# qc_board_V3.net
KiCad netlist of a schematic drawn in EAGLE
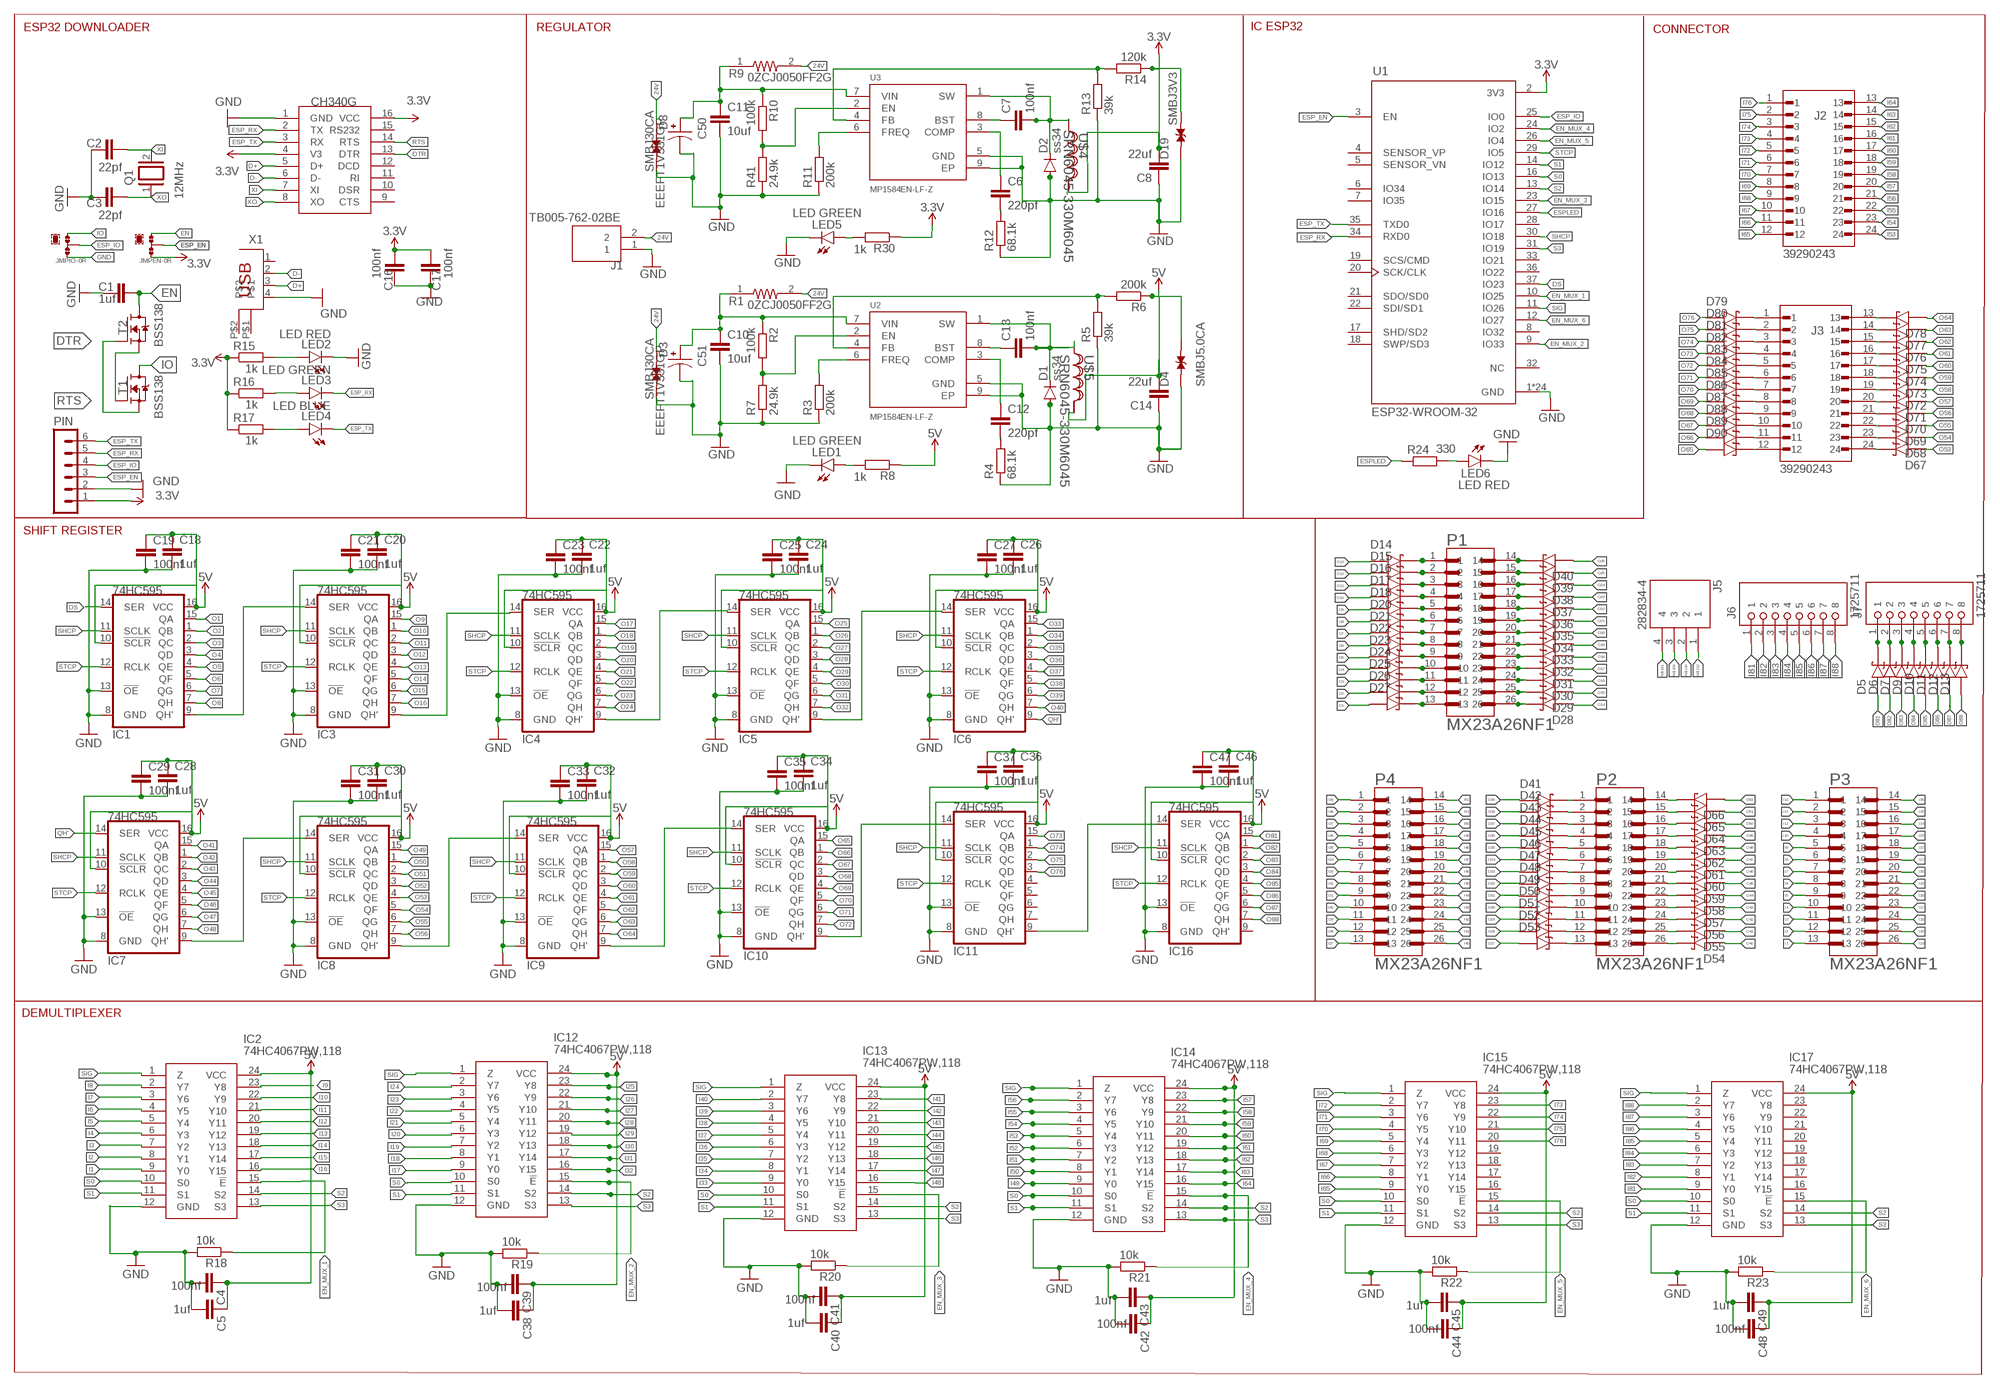
[diagram p0: schematic, sheet 1]

(export (version "E")
  (design (tool "Eeschema 10.0.6"))
  (components
    (comp (ref "C1")
      (value "1uf")
      (footprint "eagle-import:C0805")
      (libsource (lib "eagle-import") (part "C-EUC0805"))
    )
    (comp (ref "C2")
      (value "22pf")
      (footprint "eagle-import:C0805")
      (libsource (lib "eagle-import") (part "C-EUC0805"))
    )
    (comp (ref "C3")
      (value "22pf")
      (footprint "eagle-import:C0805")
      (libsource (lib "eagle-import") (part "C-EUC0805"))
    )
    (comp (ref "C4")
      (value "100nf")
      (footprint "eagle-import:C0805")
      (libsource (lib "eagle-import") (part "C-EUC0805"))
    )
    (comp (ref "C5")
      (value "1uf")
      (footprint "eagle-import:C0805")
      (libsource (lib "eagle-import") (part "C-EUC0805"))
    )
    (comp (ref "C6")
      (value "220pf")
      (footprint "eagle-import:C0805")
      (libsource (lib "eagle-import") (part "C-EUC0805"))
    )
    (comp (ref "C7")
      (value "100nf")
      (footprint "eagle-import:C0805")
      (libsource (lib "eagle-import") (part "C-EUC0805"))
    )
    (comp (ref "C8")
      (value "22uf")
      (footprint "eagle-import:C0805")
      (libsource (lib "eagle-import") (part "C-EUC0805"))
    )
    (comp (ref "C10")
      (value "10uf")
      (footprint "eagle-import:C0805")
      (libsource (lib "eagle-import") (part "C-EUC0805"))
    )
    (comp (ref "C11")
      (value "10uf")
      (footprint "eagle-import:C0805")
      (libsource (lib "eagle-import") (part "C-EUC0805"))
    )
    (comp (ref "C12")
      (value "220pf")
      (footprint "eagle-import:C0805")
      (libsource (lib "eagle-import") (part "C-EUC0805"))
    )
    (comp (ref "C13")
      (value "100nf")
      (footprint "eagle-import:C0805")
      (libsource (lib "eagle-import") (part "C-EUC0805"))
    )
    (comp (ref "C14")
      (value "22uf")
      (footprint "eagle-import:C0805")
      (libsource (lib "eagle-import") (part "C-EUC0805"))
    )
    (comp (ref "C16")
      (value "100nf")
      (footprint "eagle-import:C0805")
      (libsource (lib "eagle-import") (part "C-EUC0805"))
    )
    (comp (ref "C17")
      (value "100nf")
      (footprint "eagle-import:C0805")
      (libsource (lib "eagle-import") (part "C-EUC0805"))
    )
    (comp (ref "C18")
      (value "1uf")
      (footprint "eagle-import:C0805")
      (libsource (lib "eagle-import") (part "C-EUC0805"))
    )
    (comp (ref "C19")
      (value "100nf")
      (footprint "eagle-import:C0805")
      (libsource (lib "eagle-import") (part "C-EUC0805"))
    )
    (comp (ref "C20")
      (value "1uf")
      (footprint "eagle-import:C0805")
      (libsource (lib "eagle-import") (part "C-EUC0805"))
    )
    (comp (ref "C21")
      (value "100nf")
      (footprint "eagle-import:C0805")
      (libsource (lib "eagle-import") (part "C-EUC0805"))
    )
    (comp (ref "C22")
      (value "1uf")
      (footprint "eagle-import:C0805")
      (libsource (lib "eagle-import") (part "C-EUC0805"))
    )
    (comp (ref "C23")
      (value "100nf")
      (footprint "eagle-import:C0805")
      (libsource (lib "eagle-import") (part "C-EUC0805"))
    )
    (comp (ref "C24")
      (value "1uf")
      (footprint "eagle-import:C0805")
      (libsource (lib "eagle-import") (part "C-EUC0805"))
    )
    (comp (ref "C25")
      (value "100nf")
      (footprint "eagle-import:C0805")
      (libsource (lib "eagle-import") (part "C-EUC0805"))
    )
    (comp (ref "C26")
      (value "1uf")
      (footprint "eagle-import:C0805")
      (libsource (lib "eagle-import") (part "C-EUC0805"))
    )
    (comp (ref "C27")
      (value "100nf")
      (footprint "eagle-import:C0805")
      (libsource (lib "eagle-import") (part "C-EUC0805"))
    )
    (comp (ref "C28")
      (value "1uf")
      (footprint "eagle-import:C0805")
      (libsource (lib "eagle-import") (part "C-EUC0805"))
    )
    (comp (ref "C29")
      (value "100nf")
      (footprint "eagle-import:C0805")
      (libsource (lib "eagle-import") (part "C-EUC0805"))
    )
    (comp (ref "C30")
      (value "1uf")
      (footprint "eagle-import:C0805")
      (libsource (lib "eagle-import") (part "C-EUC0805"))
    )
    (comp (ref "C31")
      (value "100nf")
      (footprint "eagle-import:C0805")
      (libsource (lib "eagle-import") (part "C-EUC0805"))
    )
    (comp (ref "C32")
      (value "1uf")
      (footprint "eagle-import:C0805")
      (libsource (lib "eagle-import") (part "C-EUC0805"))
    )
    (comp (ref "C33")
      (value "100nf")
      (footprint "eagle-import:C0805")
      (libsource (lib "eagle-import") (part "C-EUC0805"))
    )
    (comp (ref "C34")
      (value "1uf")
      (footprint "eagle-import:C0805")
      (libsource (lib "eagle-import") (part "C-EUC0805"))
    )
    (comp (ref "C35")
      (value "100nf")
      (footprint "eagle-import:C0805")
      (libsource (lib "eagle-import") (part "C-EUC0805"))
    )
    (comp (ref "C36")
      (value "1uf")
      (footprint "eagle-import:C0805")
      (libsource (lib "eagle-import") (part "C-EUC0805"))
    )
    (comp (ref "C37")
      (value "100nf")
      (footprint "eagle-import:C0805")
      (libsource (lib "eagle-import") (part "C-EUC0805"))
    )
    (comp (ref "C38")
      (value "1uf")
      (footprint "eagle-import:C0805")
      (libsource (lib "eagle-import") (part "C-EUC0805"))
    )
    (comp (ref "C39")
      (value "100nf")
      (footprint "eagle-import:C0805")
      (libsource (lib "eagle-import") (part "C-EUC0805"))
    )
    (comp (ref "C40")
      (value "1uf")
      (footprint "eagle-import:C0805")
      (libsource (lib "eagle-import") (part "C-EUC0805"))
    )
    (comp (ref "C41")
      (value "100nf")
      (footprint "eagle-import:C0805")
      (libsource (lib "eagle-import") (part "C-EUC0805"))
    )
    (comp (ref "C42")
      (value "100nf")
      (footprint "eagle-import:C0805")
      (libsource (lib "eagle-import") (part "C-EUC0805"))
    )
    (comp (ref "C43")
      (value "1uf")
      (footprint "eagle-import:C0805")
      (libsource (lib "eagle-import") (part "C-EUC0805"))
    )
    (comp (ref "C44")
      (value "100nf")
      (footprint "eagle-import:C0805")
      (libsource (lib "eagle-import") (part "C-EUC0805"))
    )
    (comp (ref "C45")
      (value "1uf")
      (footprint "eagle-import:C0805")
      (libsource (lib "eagle-import") (part "C-EUC0805"))
    )
    (comp (ref "C46")
      (value "1uf")
      (footprint "eagle-import:C0805")
      (libsource (lib "eagle-import") (part "C-EUC0805"))
    )
    (comp (ref "C47")
      (value "100nf")
      (footprint "eagle-import:C0805")
      (libsource (lib "eagle-import") (part "C-EUC0805"))
    )
    (comp (ref "C48")
      (value "100nf")
      (footprint "eagle-import:C0805")
      (libsource (lib "eagle-import") (part "C-EUC0805"))
    )
    (comp (ref "C49")
      (value "1uf")
      (footprint "eagle-import:C0805")
      (libsource (lib "eagle-import") (part "C-EUC0805"))
    )
    (comp (ref "C50")
      (value "EEEFT1V331GP")
      (footprint "eagle-import:CAP_EEEFT1V331GP")
      (fields (field (name "MF") "Panasonic"))
      (libsource (lib "eagle-import") (part "EEEFT1V331GP"))
    )
    (comp (ref "C51")
      (value "EEEFT1V331GP")
      (footprint "eagle-import:CAP_EEEFT1V331GP")
      (fields (field (name "MF") "Panasonic"))
      (libsource (lib "eagle-import") (part "EEEFT1V331GP"))
    )
    (comp (ref "D1")
      (value "ss34")
      (footprint "eagle-import:SMB")
      (libsource (lib "eagle-import") (part "DIODE-SMB"))
    )
    (comp (ref "D2")
      (value "ss34")
      (footprint "eagle-import:SMB")
      (libsource (lib "eagle-import") (part "DIODE-SMB"))
    )
    (comp (ref "D3")
      (value "SMBJ30CA")
      (footprint "eagle-import:DIOM4336X265N")
      (fields (field (name "MF") "Taiwan Semiconductor Corporation"))
      (libsource (lib "eagle-import") (part "SMBJ30CA"))
    )
    (comp (ref "D4")
      (value "SMBJ5.0CA")
      (footprint "eagle-import:DIOM4336X265N")
      (fields (field (name "MF") "Taiwan Semiconductor"))
      (libsource (lib "eagle-import") (part "SMBJ5.0CA"))
    )
    (comp (ref "D5")
      (value "1N5819HW-7")
      (footprint "eagle-import:SOD3715X145N")
      (fields (field (name "MF") "Diodes Inc."))
      (libsource (lib "eagle-import") (part "1N5819HW-7"))
    )
    (comp (ref "D6")
      (value "1N5819HW-7")
      (footprint "eagle-import:SOD3715X145N")
      (fields (field (name "MF") "Diodes Inc."))
      (libsource (lib "eagle-import") (part "1N5819HW-7"))
    )
    (comp (ref "D7")
      (value "1N5819HW-7")
      (footprint "eagle-import:SOD3715X145N")
      (fields (field (name "MF") "Diodes Inc."))
      (libsource (lib "eagle-import") (part "1N5819HW-7"))
    )
    (comp (ref "D8")
      (value "SMBJ30CA")
      (footprint "eagle-import:DIOM4336X265N")
      (fields (field (name "MF") "Taiwan Semiconductor Corporation"))
      (libsource (lib "eagle-import") (part "SMBJ30CA"))
    )
    (comp (ref "D9")
      (value "1N5819HW-7")
      (footprint "eagle-import:SOD3715X145N")
      (fields (field (name "MF") "Diodes Inc."))
      (libsource (lib "eagle-import") (part "1N5819HW-7"))
    )
    (comp (ref "D10")
      (value "1N5819HW-7")
      (footprint "eagle-import:SOD3715X145N")
      (fields (field (name "MF") "Diodes Inc."))
      (libsource (lib "eagle-import") (part "1N5819HW-7"))
    )
    (comp (ref "D11")
      (value "1N5819HW-7")
      (footprint "eagle-import:SOD3715X145N")
      (fields (field (name "MF") "Diodes Inc."))
      (libsource (lib "eagle-import") (part "1N5819HW-7"))
    )
    (comp (ref "D12")
      (value "1N5819HW-7")
      (footprint "eagle-import:SOD3715X145N")
      (fields (field (name "MF") "Diodes Inc."))
      (libsource (lib "eagle-import") (part "1N5819HW-7"))
    )
    (comp (ref "D13")
      (value "1N5819HW-7")
      (footprint "eagle-import:SOD3715X145N")
      (fields (field (name "MF") "Diodes Inc."))
      (libsource (lib "eagle-import") (part "1N5819HW-7"))
    )
    (comp (ref "D14")
      (value "1N5819HW-7")
      (footprint "eagle-import:SOD3715X145N")
      (fields (field (name "MF") "Diodes Inc."))
      (libsource (lib "eagle-import") (part "1N5819HW-7"))
    )
    (comp (ref "D15")
      (value "1N5819HW-7")
      (footprint "eagle-import:SOD3715X145N")
      (fields (field (name "MF") "Diodes Inc."))
      (libsource (lib "eagle-import") (part "1N5819HW-7"))
    )
    (comp (ref "D16")
      (value "1N5819HW-7")
      (footprint "eagle-import:SOD3715X145N")
      (fields (field (name "MF") "Diodes Inc."))
      (libsource (lib "eagle-import") (part "1N5819HW-7"))
    )
    (comp (ref "D17")
      (value "1N5819HW-7")
      (footprint "eagle-import:SOD3715X145N")
      (fields (field (name "MF") "Diodes Inc."))
      (libsource (lib "eagle-import") (part "1N5819HW-7"))
    )
    (comp (ref "D18")
      (value "1N5819HW-7")
      (footprint "eagle-import:SOD3715X145N")
      (fields (field (name "MF") "Diodes Inc."))
      (libsource (lib "eagle-import") (part "1N5819HW-7"))
    )
    (comp (ref "D19")
      (value "SMBJ3V3")
      (footprint "eagle-import:DIOM4336X265N")
      (fields (field (name "MF") "Taiwan Semiconductor Corporation") (field (name "MP") "SMBJ30CA"))
      (libsource (lib "eagle-import") (part "SMBJ3V3"))
    )
    (comp (ref "D20")
      (value "1N5819HW-7")
      (footprint "eagle-import:SOD3715X145N")
      (fields (field (name "MF") "Diodes Inc."))
      (libsource (lib "eagle-import") (part "1N5819HW-7"))
    )
    (comp (ref "D21")
      (value "1N5819HW-7")
      (footprint "eagle-import:SOD3715X145N")
      (fields (field (name "MF") "Diodes Inc."))
      (libsource (lib "eagle-import") (part "1N5819HW-7"))
    )
    (comp (ref "D22")
      (value "1N5819HW-7")
      (footprint "eagle-import:SOD3715X145N")
      (fields (field (name "MF") "Diodes Inc."))
      (libsource (lib "eagle-import") (part "1N5819HW-7"))
    )
    (comp (ref "D23")
      (value "1N5819HW-7")
      (footprint "eagle-import:SOD3715X145N")
      (fields (field (name "MF") "Diodes Inc."))
      (libsource (lib "eagle-import") (part "1N5819HW-7"))
    )
    (comp (ref "D24")
      (value "1N5819HW-7")
      (footprint "eagle-import:SOD3715X145N")
      (fields (field (name "MF") "Diodes Inc."))
      (libsource (lib "eagle-import") (part "1N5819HW-7"))
    )
    (comp (ref "D25")
      (value "1N5819HW-7")
      (footprint "eagle-import:SOD3715X145N")
      (fields (field (name "MF") "Diodes Inc."))
      (libsource (lib "eagle-import") (part "1N5819HW-7"))
    )
    (comp (ref "D26")
      (value "1N5819HW-7")
      (footprint "eagle-import:SOD3715X145N")
      (fields (field (name "MF") "Diodes Inc."))
      (libsource (lib "eagle-import") (part "1N5819HW-7"))
    )
    (comp (ref "D27")
      (value "1N5819HW-7")
      (footprint "eagle-import:SOD3715X145N")
      (fields (field (name "MF") "Diodes Inc."))
      (libsource (lib "eagle-import") (part "1N5819HW-7"))
    )
    (comp (ref "D28")
      (value "1N5819HW-7")
      (footprint "eagle-import:SOD3715X145N")
      (fields (field (name "MF") "Diodes Inc."))
      (libsource (lib "eagle-import") (part "1N5819HW-7"))
    )
    (comp (ref "D29")
      (value "1N5819HW-7")
      (footprint "eagle-import:SOD3715X145N")
      (fields (field (name "MF") "Diodes Inc."))
      (libsource (lib "eagle-import") (part "1N5819HW-7"))
    )
    (comp (ref "D30")
      (value "1N5819HW-7")
      (footprint "eagle-import:SOD3715X145N")
      (fields (field (name "MF") "Diodes Inc."))
      (libsource (lib "eagle-import") (part "1N5819HW-7"))
    )
    (comp (ref "D31")
      (value "1N5819HW-7")
      (footprint "eagle-import:SOD3715X145N")
      (fields (field (name "MF") "Diodes Inc."))
      (libsource (lib "eagle-import") (part "1N5819HW-7"))
    )
    (comp (ref "D32")
      (value "1N5819HW-7")
      (footprint "eagle-import:SOD3715X145N")
      (fields (field (name "MF") "Diodes Inc."))
      (libsource (lib "eagle-import") (part "1N5819HW-7"))
    )
    (comp (ref "D33")
      (value "1N5819HW-7")
      (footprint "eagle-import:SOD3715X145N")
      (fields (field (name "MF") "Diodes Inc."))
      (libsource (lib "eagle-import") (part "1N5819HW-7"))
    )
    (comp (ref "D34")
      (value "1N5819HW-7")
      (footprint "eagle-import:SOD3715X145N")
      (fields (field (name "MF") "Diodes Inc."))
      (libsource (lib "eagle-import") (part "1N5819HW-7"))
    )
    (comp (ref "D35")
      (value "1N5819HW-7")
      (footprint "eagle-import:SOD3715X145N")
      (fields (field (name "MF") "Diodes Inc."))
      (libsource (lib "eagle-import") (part "1N5819HW-7"))
    )
    (comp (ref "D36")
      (value "1N5819HW-7")
      (footprint "eagle-import:SOD3715X145N")
      (fields (field (name "MF") "Diodes Inc."))
      (libsource (lib "eagle-import") (part "1N5819HW-7"))
    )
    (comp (ref "D37")
      (value "1N5819HW-7")
      (footprint "eagle-import:SOD3715X145N")
      (fields (field (name "MF") "Diodes Inc."))
      (libsource (lib "eagle-import") (part "1N5819HW-7"))
    )
    (comp (ref "D38")
      (value "1N5819HW-7")
      (footprint "eagle-import:SOD3715X145N")
      (fields (field (name "MF") "Diodes Inc."))
      (libsource (lib "eagle-import") (part "1N5819HW-7"))
    )
    (comp (ref "D39")
      (value "1N5819HW-7")
      (footprint "eagle-import:SOD3715X145N")
      (fields (field (name "MF") "Diodes Inc."))
      (libsource (lib "eagle-import") (part "1N5819HW-7"))
    )
    (comp (ref "D40")
      (value "1N5819HW-7")
      (footprint "eagle-import:SOD3715X145N")
      (fields (field (name "MF") "Diodes Inc."))
      (libsource (lib "eagle-import") (part "1N5819HW-7"))
    )
    (comp (ref "D41")
      (value "1N5819HW-7")
      (footprint "eagle-import:SOD3715X145N")
      (fields (field (name "MF") "Diodes Inc."))
      (libsource (lib "eagle-import") (part "1N5819HW-7"))
    )
    (comp (ref "D42")
      (value "1N5819HW-7")
      (footprint "eagle-import:SOD3715X145N")
      (fields (field (name "MF") "Diodes Inc."))
      (libsource (lib "eagle-import") (part "1N5819HW-7"))
    )
    (comp (ref "D43")
      (value "1N5819HW-7")
      (footprint "eagle-import:SOD3715X145N")
      (fields (field (name "MF") "Diodes Inc."))
      (libsource (lib "eagle-import") (part "1N5819HW-7"))
    )
    (comp (ref "D44")
      (value "1N5819HW-7")
      (footprint "eagle-import:SOD3715X145N")
      (fields (field (name "MF") "Diodes Inc."))
      (libsource (lib "eagle-import") (part "1N5819HW-7"))
    )
    (comp (ref "D45")
      (value "1N5819HW-7")
      (footprint "eagle-import:SOD3715X145N")
      (fields (field (name "MF") "Diodes Inc."))
      (libsource (lib "eagle-import") (part "1N5819HW-7"))
    )
    (comp (ref "D46")
      (value "1N5819HW-7")
      (footprint "eagle-import:SOD3715X145N")
      (fields (field (name "MF") "Diodes Inc."))
      (libsource (lib "eagle-import") (part "1N5819HW-7"))
    )
    (comp (ref "D47")
      (value "1N5819HW-7")
      (footprint "eagle-import:SOD3715X145N")
      (fields (field (name "MF") "Diodes Inc."))
      (libsource (lib "eagle-import") (part "1N5819HW-7"))
    )
    (comp (ref "D48")
      (value "1N5819HW-7")
      (footprint "eagle-import:SOD3715X145N")
      (fields (field (name "MF") "Diodes Inc."))
      (libsource (lib "eagle-import") (part "1N5819HW-7"))
    )
    (comp (ref "D49")
      (value "1N5819HW-7")
      (footprint "eagle-import:SOD3715X145N")
      (fields (field (name "MF") "Diodes Inc."))
      (libsource (lib "eagle-import") (part "1N5819HW-7"))
    )
    (comp (ref "D50")
      (value "1N5819HW-7")
      (footprint "eagle-import:SOD3715X145N")
      (fields (field (name "MF") "Diodes Inc."))
      (libsource (lib "eagle-import") (part "1N5819HW-7"))
    )
    (comp (ref "D51")
      (value "1N5819HW-7")
      (footprint "eagle-import:SOD3715X145N")
      (fields (field (name "MF") "Diodes Inc."))
      (libsource (lib "eagle-import") (part "1N5819HW-7"))
    )
    (comp (ref "D52")
      (value "1N5819HW-7")
      (footprint "eagle-import:SOD3715X145N")
      (fields (field (name "MF") "Diodes Inc."))
      (libsource (lib "eagle-import") (part "1N5819HW-7"))
    )
    (comp (ref "D53")
      (value "1N5819HW-7")
      (footprint "eagle-import:SOD3715X145N")
      (fields (field (name "MF") "Diodes Inc."))
      (libsource (lib "eagle-import") (part "1N5819HW-7"))
    )
    (comp (ref "D54")
      (value "1N5819HW-7")
      (footprint "eagle-import:SOD3715X145N")
      (fields (field (name "MF") "Diodes Inc."))
      (libsource (lib "eagle-import") (part "1N5819HW-7"))
    )
    (comp (ref "D55")
      (value "1N5819HW-7")
      (footprint "eagle-import:SOD3715X145N")
      (fields (field (name "MF") "Diodes Inc."))
      (libsource (lib "eagle-import") (part "1N5819HW-7"))
    )
    (comp (ref "D56")
      (value "1N5819HW-7")
      (footprint "eagle-import:SOD3715X145N")
      (fields (field (name "MF") "Diodes Inc."))
      (libsource (lib "eagle-import") (part "1N5819HW-7"))
    )
    (comp (ref "D57")
      (value "1N5819HW-7")
      (footprint "eagle-import:SOD3715X145N")
      (fields (field (name "MF") "Diodes Inc."))
      (libsource (lib "eagle-import") (part "1N5819HW-7"))
    )
    (comp (ref "D58")
      (value "1N5819HW-7")
      (footprint "eagle-import:SOD3715X145N")
      (fields (field (name "MF") "Diodes Inc."))
      (libsource (lib "eagle-import") (part "1N5819HW-7"))
    )
    (comp (ref "D59")
      (value "1N5819HW-7")
      (footprint "eagle-import:SOD3715X145N")
      (fields (field (name "MF") "Diodes Inc."))
      (libsource (lib "eagle-import") (part "1N5819HW-7"))
    )
    (comp (ref "D60")
      (value "1N5819HW-7")
      (footprint "eagle-import:SOD3715X145N")
      (fields (field (name "MF") "Diodes Inc."))
      (libsource (lib "eagle-import") (part "1N5819HW-7"))
    )
    (comp (ref "D61")
      (value "1N5819HW-7")
      (footprint "eagle-import:SOD3715X145N")
      (fields (field (name "MF") "Diodes Inc."))
      (libsource (lib "eagle-import") (part "1N5819HW-7"))
    )
    (comp (ref "D62")
      (value "1N5819HW-7")
      (footprint "eagle-import:SOD3715X145N")
      (fields (field (name "MF") "Diodes Inc."))
      (libsource (lib "eagle-import") (part "1N5819HW-7"))
    )
    (comp (ref "D63")
      (value "1N5819HW-7")
      (footprint "eagle-import:SOD3715X145N")
      (fields (field (name "MF") "Diodes Inc."))
      (libsource (lib "eagle-import") (part "1N5819HW-7"))
    )
    (comp (ref "D64")
      (value "1N5819HW-7")
      (footprint "eagle-import:SOD3715X145N")
      (fields (field (name "MF") "Diodes Inc."))
      (libsource (lib "eagle-import") (part "1N5819HW-7"))
    )
    (comp (ref "D65")
      (value "1N5819HW-7")
      (footprint "eagle-import:SOD3715X145N")
      (fields (field (name "MF") "Diodes Inc."))
      (libsource (lib "eagle-import") (part "1N5819HW-7"))
    )
    (comp (ref "D66")
      (value "1N5819HW-7")
      (footprint "eagle-import:SOD3715X145N")
      (fields (field (name "MF") "Diodes Inc."))
      (libsource (lib "eagle-import") (part "1N5819HW-7"))
    )
    (comp (ref "D67")
      (value "1N5819HW-7")
      (footprint "eagle-import:SOD3715X145N")
      (fields (field (name "MF") "Diodes Inc."))
      (libsource (lib "eagle-import") (part "1N5819HW-7"))
    )
    (comp (ref "D68")
      (value "1N5819HW-7")
      (footprint "eagle-import:SOD3715X145N")
      (fields (field (name "MF") "Diodes Inc."))
      (libsource (lib "eagle-import") (part "1N5819HW-7"))
    )
    (comp (ref "D69")
      (value "1N5819HW-7")
      (footprint "eagle-import:SOD3715X145N")
      (fields (field (name "MF") "Diodes Inc."))
      (libsource (lib "eagle-import") (part "1N5819HW-7"))
    )
    (comp (ref "D70")
      (value "1N5819HW-7")
      (footprint "eagle-import:SOD3715X145N")
      (fields (field (name "MF") "Diodes Inc."))
      (libsource (lib "eagle-import") (part "1N5819HW-7"))
    )
    (comp (ref "D71")
      (value "1N5819HW-7")
      (footprint "eagle-import:SOD3715X145N")
      (fields (field (name "MF") "Diodes Inc."))
      (libsource (lib "eagle-import") (part "1N5819HW-7"))
    )
    (comp (ref "D72")
      (value "1N5819HW-7")
      (footprint "eagle-import:SOD3715X145N")
      (fields (field (name "MF") "Diodes Inc."))
      (libsource (lib "eagle-import") (part "1N5819HW-7"))
    )
    (comp (ref "D73")
      (value "1N5819HW-7")
      (footprint "eagle-import:SOD3715X145N")
      (fields (field (name "MF") "Diodes Inc."))
      (libsource (lib "eagle-import") (part "1N5819HW-7"))
    )
    (comp (ref "D74")
      (value "1N5819HW-7")
      (footprint "eagle-import:SOD3715X145N")
      (fields (field (name "MF") "Diodes Inc."))
      (libsource (lib "eagle-import") (part "1N5819HW-7"))
    )
    (comp (ref "D75")
      (value "1N5819HW-7")
      (footprint "eagle-import:SOD3715X145N")
      (fields (field (name "MF") "Diodes Inc."))
      (libsource (lib "eagle-import") (part "1N5819HW-7"))
    )
    (comp (ref "D76")
      (value "1N5819HW-7")
      (footprint "eagle-import:SOD3715X145N")
      (fields (field (name "MF") "Diodes Inc."))
      (libsource (lib "eagle-import") (part "1N5819HW-7"))
    )
    (comp (ref "D77")
      (value "1N5819HW-7")
      (footprint "eagle-import:SOD3715X145N")
      (fields (field (name "MF") "Diodes Inc."))
      (libsource (lib "eagle-import") (part "1N5819HW-7"))
    )
    (comp (ref "D78")
      (value "1N5819HW-7")
      (footprint "eagle-import:SOD3715X145N")
      (fields (field (name "MF") "Diodes Inc."))
      (libsource (lib "eagle-import") (part "1N5819HW-7"))
    )
    (comp (ref "D79")
      (value "1N5819HW-7")
      (footprint "eagle-import:SOD3715X145N")
      (fields (field (name "MF") "Diodes Inc."))
      (libsource (lib "eagle-import") (part "1N5819HW-7"))
    )
    (comp (ref "D80")
      (value "1N5819HW-7")
      (footprint "eagle-import:SOD3715X145N")
      (fields (field (name "MF") "Diodes Inc."))
      (libsource (lib "eagle-import") (part "1N5819HW-7"))
    )
    (comp (ref "D81")
      (value "1N5819HW-7")
      (footprint "eagle-import:SOD3715X145N")
      (fields (field (name "MF") "Diodes Inc."))
      (libsource (lib "eagle-import") (part "1N5819HW-7"))
    )
    (comp (ref "D82")
      (value "1N5819HW-7")
      (footprint "eagle-import:SOD3715X145N")
      (fields (field (name "MF") "Diodes Inc."))
      (libsource (lib "eagle-import") (part "1N5819HW-7"))
    )
    (comp (ref "D83")
      (value "1N5819HW-7")
      (footprint "eagle-import:SOD3715X145N")
      (fields (field (name "MF") "Diodes Inc."))
      (libsource (lib "eagle-import") (part "1N5819HW-7"))
    )
    (comp (ref "D84")
      (value "1N5819HW-7")
      (footprint "eagle-import:SOD3715X145N")
      (fields (field (name "MF") "Diodes Inc."))
      (libsource (lib "eagle-import") (part "1N5819HW-7"))
    )
    (comp (ref "D85")
      (value "1N5819HW-7")
      (footprint "eagle-import:SOD3715X145N")
      (fields (field (name "MF") "Diodes Inc."))
      (libsource (lib "eagle-import") (part "1N5819HW-7"))
    )
    (comp (ref "D86")
      (value "1N5819HW-7")
      (footprint "eagle-import:SOD3715X145N")
      (fields (field (name "MF") "Diodes Inc."))
      (libsource (lib "eagle-import") (part "1N5819HW-7"))
    )
    (comp (ref "D87")
      (value "1N5819HW-7")
      (footprint "eagle-import:SOD3715X145N")
      (fields (field (name "MF") "Diodes Inc."))
      (libsource (lib "eagle-import") (part "1N5819HW-7"))
    )
    (comp (ref "D88")
      (value "1N5819HW-7")
      (footprint "eagle-import:SOD3715X145N")
      (fields (field (name "MF") "Diodes Inc."))
      (libsource (lib "eagle-import") (part "1N5819HW-7"))
    )
    (comp (ref "D89")
      (value "1N5819HW-7")
      (footprint "eagle-import:SOD3715X145N")
      (fields (field (name "MF") "Diodes Inc."))
      (libsource (lib "eagle-import") (part "1N5819HW-7"))
    )
    (comp (ref "D90")
      (value "1N5819HW-7")
      (footprint "eagle-import:SOD3715X145N")
      (fields (field (name "MF") "Diodes Inc."))
      (libsource (lib "eagle-import") (part "1N5819HW-7"))
    )
    (comp (ref "IC1")
      (value "74HC595")
      (footprint "eagle-import:SO16")
      (fields (field (name "MF") "Nexperia"))
      (libsource (lib "eagle-import") (part "74HC595"))
    )
    (comp (ref "IC2")
      (value "74HC4067PW,118")
      (footprint "eagle-import:SOP65P640X110-24N")
      (fields (field (name "MOUSER_PART_NUMBER") "771-74HC4067PW-T"))
      (libsource (lib "eagle-import") (part "74HC4067PW,118"))
    )
    (comp (ref "IC3")
      (value "74HC595")
      (footprint "eagle-import:SO16")
      (fields (field (name "MF") "Nexperia"))
      (libsource (lib "eagle-import") (part "74HC595"))
    )
    (comp (ref "IC4")
      (value "74HC595")
      (footprint "eagle-import:SO16")
      (fields (field (name "MF") "Nexperia"))
      (libsource (lib "eagle-import") (part "74HC595"))
    )
    (comp (ref "IC5")
      (value "74HC595")
      (footprint "eagle-import:SO16")
      (fields (field (name "MF") "Nexperia"))
      (libsource (lib "eagle-import") (part "74HC595"))
    )
    (comp (ref "IC6")
      (value "74HC595")
      (footprint "eagle-import:SO16")
      (fields (field (name "MF") "Nexperia"))
      (libsource (lib "eagle-import") (part "74HC595"))
    )
    (comp (ref "IC7")
      (value "74HC595")
      (footprint "eagle-import:SO16")
      (fields (field (name "MF") "Nexperia"))
      (libsource (lib "eagle-import") (part "74HC595"))
    )
    (comp (ref "IC8")
      (value "74HC595")
      (footprint "eagle-import:SO16")
      (fields (field (name "MF") "Nexperia"))
      (libsource (lib "eagle-import") (part "74HC595"))
    )
    (comp (ref "IC9")
      (value "74HC595")
      (footprint "eagle-import:SO16")
      (fields (field (name "MF") "Nexperia"))
      (libsource (lib "eagle-import") (part "74HC595"))
    )
    (comp (ref "IC10")
      (value "74HC595")
      (footprint "eagle-import:SO16")
      (fields (field (name "MF") "Nexperia"))
      (libsource (lib "eagle-import") (part "74HC595"))
    )
    (comp (ref "IC11")
      (value "74HC595")
      (footprint "eagle-import:SO16")
      (fields (field (name "MF") "Nexperia"))
      (libsource (lib "eagle-import") (part "74HC595"))
    )
    (comp (ref "IC12")
      (value "74HC4067PW,118")
      (footprint "eagle-import:SOP65P640X110-24N")
      (fields (field (name "MOUSER_PART_NUMBER") "771-74HC4067PW-T"))
      (libsource (lib "eagle-import") (part "74HC4067PW,118"))
    )
    (comp (ref "IC13")
      (value "74HC4067PW,118")
      (footprint "eagle-import:SOP65P640X110-24N")
      (fields (field (name "MOUSER_PART_NUMBER") "771-74HC4067PW-T"))
      (libsource (lib "eagle-import") (part "74HC4067PW,118"))
    )
    (comp (ref "IC14")
      (value "74HC4067PW,118")
      (footprint "eagle-import:SOP65P640X110-24N")
      (fields (field (name "MOUSER_PART_NUMBER") "771-74HC4067PW-T"))
      (libsource (lib "eagle-import") (part "74HC4067PW,118"))
    )
    (comp (ref "IC15")
      (value "74HC4067PW,118")
      (footprint "eagle-import:SOP65P640X110-24N")
      (fields (field (name "MOUSER_PART_NUMBER") "771-74HC4067PW-T"))
      (libsource (lib "eagle-import") (part "74HC4067PW,118"))
    )
    (comp (ref "IC16")
      (value "74HC595")
      (footprint "eagle-import:SO16")
      (fields (field (name "MF") "Nexperia"))
      (libsource (lib "eagle-import") (part "74HC595"))
    )
    (comp (ref "IC17")
      (value "74HC4067PW,118")
      (footprint "eagle-import:SOP65P640X110-24N")
      (fields (field (name "MOUSER_PART_NUMBER") "771-74HC4067PW-T"))
      (libsource (lib "eagle-import") (part "74HC4067PW,118"))
    )
    (comp (ref "J1")
      (value "TB005-762-02BE")
      (footprint "eagle-import:CUI_TB005-762-02BE")
      (fields (field (name "MF") "Same Sky"))
      (libsource (lib "eagle-import") (part "TB005-762-02BE"))
    )
    (comp (ref "J2")
      (value "39290243")
      (footprint "eagle-import:MOLEX_39290243")
      (fields (field (name "MF") "Molex Connector") (field (name "MP") "39-29-0243"))
      (libsource (lib "eagle-import") (part "39290243"))
    )
    (comp (ref "J3")
      (value "39290243")
      (footprint "eagle-import:MOLEX_39290243")
      (fields (field (name "MF") "Molex Connector") (field (name "MP") "39-29-0243"))
      (libsource (lib "eagle-import") (part "39290243"))
    )
    (comp (ref "J5")
      (value "282834-4")
      (footprint "eagle-import:TE_282834-4")
      (fields (field (name "MF") "TE Connectivity"))
      (libsource (lib "eagle-import") (part "282834-4"))
    )
    (comp (ref "J6")
      (value "1725711")
      (footprint "eagle-import:PHOENIX_1725711")
      (fields (field (name "MF") "Phoenix Contact"))
      (libsource (lib "eagle-import") (part "1725711"))
    )
    (comp (ref "J7")
      (value "1725711")
      (footprint "eagle-import:PHOENIX_1725711")
      (fields (field (name "MF") "Phoenix Contact"))
      (libsource (lib "eagle-import") (part "1725711"))
    )
    (comp (ref "JMPEN")
      (value "0R-JUMPB")
      (footprint "eagle-import:B0R-JMP")
      (libsource (lib "eagle-import") (part "0R-JUMPB"))
    )
    (comp (ref "JMPIO")
      (value "0R-JUMPB")
      (footprint "eagle-import:B0R-JMP")
      (libsource (lib "eagle-import") (part "0R-JUMPB"))
    )
    (comp (ref "LED1")
      (value "LED GREEN")
      (footprint "eagle-import:CHIP-LED0805")
      (libsource (lib "eagle-import") (part "LEDCHIP-LED0805"))
    )
    (comp (ref "LED2")
      (value "LED RED")
      (footprint "eagle-import:CHIPLED_0805")
      (libsource (lib "eagle-import") (part "LEDCHIPLED_0805"))
    )
    (comp (ref "LED3")
      (value "LED GREEN")
      (footprint "eagle-import:CHIPLED_0805")
      (libsource (lib "eagle-import") (part "LEDCHIPLED_0805"))
    )
    (comp (ref "LED4")
      (value "LED BLUE")
      (footprint "eagle-import:CHIPLED_0805")
      (libsource (lib "eagle-import") (part "LEDCHIPLED_0805"))
    )
    (comp (ref "LED5")
      (value "LED GREEN")
      (footprint "eagle-import:CHIP-LED0805")
      (libsource (lib "eagle-import") (part "LEDCHIP-LED0805"))
    )
    (comp (ref "LED6")
      (value "LED RED")
      (footprint "eagle-import:CHIP-LED0805")
      (libsource (lib "eagle-import") (part "LEDCHIP-LED0805"))
    )
    (comp (ref "P1")
      (value "MX23A26NF1")
      (footprint "eagle-import:JAE_MX23A26NF1")
      (fields (field (name "MF") "JAE Electronics"))
      (libsource (lib "eagle-import") (part "MX23A26NF1"))
    )
    (comp (ref "P2")
      (value "MX23A26NF1")
      (footprint "eagle-import:JAE_MX23A26NF1")
      (fields (field (name "MF") "JAE Electronics"))
      (libsource (lib "eagle-import") (part "MX23A26NF1"))
    )
    (comp (ref "P3")
      (value "MX23A26NF1")
      (footprint "eagle-import:JAE_MX23A26NF1")
      (fields (field (name "MF") "JAE Electronics"))
      (libsource (lib "eagle-import") (part "MX23A26NF1"))
    )
    (comp (ref "P4")
      (value "MX23A26NF1")
      (footprint "eagle-import:JAE_MX23A26NF1")
      (fields (field (name "MF") "JAE Electronics"))
      (libsource (lib "eagle-import") (part "MX23A26NF1"))
    )
    (comp (ref "PIN")
      (value "MA06-1")
      (footprint "eagle-import:MA06-1")
      (libsource (lib "eagle-import") (part "MA06-1"))
    )
    (comp (ref "Q1")
      (value "12MHz")
      (footprint "eagle-import:QS")
      (libsource (lib "eagle-import") (part "XTAL/S"))
    )
    (comp (ref "R1")
      (value "0ZCJ0050FF2G")
      (footprint "eagle-import:RESC3216X125N")
      (fields (field (name "MF") "Bel Fuse"))
      (libsource (lib "eagle-import") (part "0ZCJ0050FF2G"))
    )
    (comp (ref "R2")
      (value "100k")
      (footprint "eagle-import:R0805")
      (libsource (lib "eagle-import") (part "rcl_334_R-EU_R0805"))
    )
    (comp (ref "R3")
      (value "200k")
      (footprint "eagle-import:R0805")
      (libsource (lib "eagle-import") (part "rcl_334_R-EU_R0805"))
    )
    (comp (ref "R4")
      (value "68.1k")
      (footprint "eagle-import:R0805")
      (libsource (lib "eagle-import") (part "rcl_334_R-EU_R0805"))
    )
    (comp (ref "R5")
      (value "39k")
      (footprint "eagle-import:R0805")
      (libsource (lib "eagle-import") (part "rcl_334_R-EU_R0805"))
    )
    (comp (ref "R6")
      (value "200k")
      (footprint "eagle-import:R0805")
      (libsource (lib "eagle-import") (part "rcl_334_R-EU_R0805"))
    )
    (comp (ref "R7")
      (value "24.9k")
      (footprint "eagle-import:R0805")
      (libsource (lib "eagle-import") (part "rcl_334_R-EU_R0805"))
    )
    (comp (ref "R8")
      (value "1k")
      (footprint "eagle-import:R0805")
      (libsource (lib "eagle-import") (part "rcl_334_R-EU_R0805"))
    )
    (comp (ref "R9")
      (value "0ZCJ0050FF2G")
      (footprint "eagle-import:RESC3216X125N")
      (fields (field (name "MF") "Bel Fuse"))
      (libsource (lib "eagle-import") (part "0ZCJ0050FF2G"))
    )
    (comp (ref "R10")
      (value "100k")
      (footprint "eagle-import:R0805")
      (libsource (lib "eagle-import") (part "rcl_334_R-EU_R0805"))
    )
    (comp (ref "R11")
      (value "200k")
      (footprint "eagle-import:R0805")
      (libsource (lib "eagle-import") (part "rcl_334_R-EU_R0805"))
    )
    (comp (ref "R12")
      (value "68.1k")
      (footprint "eagle-import:R0805")
      (libsource (lib "eagle-import") (part "rcl_334_R-EU_R0805"))
    )
    (comp (ref "R13")
      (value "39k")
      (footprint "eagle-import:R0805")
      (libsource (lib "eagle-import") (part "rcl_334_R-EU_R0805"))
    )
    (comp (ref "R14")
      (value "120k")
      (footprint "eagle-import:R0805")
      (libsource (lib "eagle-import") (part "rcl_334_R-EU_R0805"))
    )
    (comp (ref "R15")
      (value "1k")
      (footprint "eagle-import:M0805")
      (libsource (lib "eagle-import") (part "R-EU_M0805"))
    )
    (comp (ref "R16")
      (value "1k")
      (footprint "eagle-import:M0805")
      (libsource (lib "eagle-import") (part "R-EU_M0805"))
    )
    (comp (ref "R17")
      (value "1k")
      (footprint "eagle-import:M0805")
      (libsource (lib "eagle-import") (part "R-EU_M0805"))
    )
    (comp (ref "R18")
      (value "10k")
      (footprint "eagle-import:M0805")
      (libsource (lib "eagle-import") (part "R-EU_M0805"))
    )
    (comp (ref "R19")
      (value "10k")
      (footprint "eagle-import:M0805")
      (libsource (lib "eagle-import") (part "R-EU_M0805"))
    )
    (comp (ref "R20")
      (value "10k")
      (footprint "eagle-import:M0805")
      (libsource (lib "eagle-import") (part "R-EU_M0805"))
    )
    (comp (ref "R21")
      (value "10k")
      (footprint "eagle-import:M0805")
      (libsource (lib "eagle-import") (part "R-EU_M0805"))
    )
    (comp (ref "R22")
      (value "10k")
      (footprint "eagle-import:M0805")
      (libsource (lib "eagle-import") (part "R-EU_M0805"))
    )
    (comp (ref "R23")
      (value "10k")
      (footprint "eagle-import:M0805")
      (libsource (lib "eagle-import") (part "R-EU_M0805"))
    )
    (comp (ref "R24")
      (value "330")
      (footprint "eagle-import:R0805")
      (libsource (lib "eagle-import") (part "rcl_334_R-EU_R0805"))
    )
    (comp (ref "R30")
      (value "1k")
      (footprint "eagle-import:R0805")
      (libsource (lib "eagle-import") (part "rcl_334_R-EU_R0805"))
    )
    (comp (ref "R41")
      (value "24.9k")
      (footprint "eagle-import:R0805")
      (libsource (lib "eagle-import") (part "rcl_334_R-EU_R0805"))
    )
    (comp (ref "T1")
      (value "BSS138")
      (footprint "eagle-import:SOT95P240X111-3N")
      (fields (field (name "MF") "ON Semiconductor"))
      (libsource (lib "eagle-import") (part "BSS138"))
    )
    (comp (ref "T2")
      (value "BSS138")
      (footprint "eagle-import:SOT95P240X111-3N")
      (fields (field (name "MF") "ON Semiconductor"))
      (libsource (lib "eagle-import") (part "BSS138"))
    )
    (comp (ref "U$3")
      (value "CH340G")
      (footprint "eagle-import:SOIC16")
      (libsource (lib "eagle-import") (part "CH340G"))
    )
    (comp (ref "U$4")
      (value "SRN6045-330M6045")
      (footprint "eagle-import:SRN6045")
      (fields (field (name "MF") "Bourns") (field (name "MP") "SRN6045-330M"))
      (libsource (lib "eagle-import") (part "SRN6045-330M6045"))
    )
    (comp (ref "U$5")
      (value "SRN6045-330M6045")
      (footprint "eagle-import:SRN6045")
      (fields (field (name "MF") "Bourns") (field (name "MP") "SRN6045-330M"))
      (libsource (lib "eagle-import") (part "SRN6045-330M6045"))
    )
    (comp (ref "U1")
      (value "ESP32-WROOM-32")
      (footprint "eagle-import:MODULE_ESP32-WROOM-32")
      (fields (field (name "MF") "Espressif Systems"))
      (libsource (lib "eagle-import") (part "ESP32-WROOM-32"))
    )
    (comp (ref "U2")
      (value "MP1584EN-LF-Z")
      (footprint "eagle-import:SOIC127P600X170-9N")
      (fields (field (name "MF") "Monolithic Power"))
      (libsource (lib "eagle-import") (part "MP1584EN-LF-Z"))
    )
    (comp (ref "U3")
      (value "MP1584EN-LF-Z")
      (footprint "eagle-import:SOIC127P600X170-9N")
      (fields (field (name "MF") "Monolithic Power"))
      (libsource (lib "eagle-import") (part "MP1584EN-LF-Z"))
    )
    (comp (ref "X1")
      (value "PN61729")
      (footprint "eagle-import:PN61729")
      (libsource (lib "eagle-import") (part "PN61729"))
    )
  )
  (nets
    (net (code "1") (name "3.3V") (class "Default")
      (node (ref "C16") (pin "1") (pinfunction "1_1") (pintype "passive"))
      (node (ref "C17") (pin "1") (pinfunction "1_1") (pintype "passive"))
      (node (ref "C8") (pin "2") (pinfunction "2_2") (pintype "passive"))
      (node (ref "D19") (pin "2") (pinfunction "2_2") (pintype "passive"))
      (node (ref "JMPEN") (pin "3") (pinfunction "3_3") (pintype "passive"))
      (node (ref "PIN") (pin "1") (pinfunction "1_1") (pintype "passive"))
      (node (ref "R14") (pin "1") (pinfunction "1_1") (pintype "passive"))
      (node (ref "R15") (pin "1") (pinfunction "1_1") (pintype "passive"))
      (node (ref "R16") (pin "1") (pinfunction "1_1") (pintype "passive"))
      (node (ref "R17") (pin "1") (pinfunction "1_1") (pintype "passive"))
      (node (ref "R30") (pin "1") (pinfunction "1_1") (pintype "passive"))
      (node (ref "U$3") (pin "16") (pinfunction "VCC_16") (pintype "bidirectional"))
      (node (ref "U$3") (pin "4") (pinfunction "V3_4") (pintype "bidirectional"))
      (node (ref "U$4") (pin "1") (pinfunction "1_1") (pintype "passive"))
      (node (ref "U1") (pin "2") (pinfunction "3V3_2") (pintype "power_in"))
    )
    (net (code "2") (name "5V") (class "Default")
      (node (ref "C14") (pin "2") (pinfunction "2_2") (pintype "passive"))
      (node (ref "C18") (pin "1") (pinfunction "1_1") (pintype "passive"))
      (node (ref "C19") (pin "1") (pinfunction "1_1") (pintype "passive"))
      (node (ref "C20") (pin "1") (pinfunction "1_1") (pintype "passive"))
      (node (ref "C21") (pin "1") (pinfunction "1_1") (pintype "passive"))
      (node (ref "C22") (pin "1") (pinfunction "1_1") (pintype "passive"))
      (node (ref "C23") (pin "1") (pinfunction "1_1") (pintype "passive"))
      (node (ref "C24") (pin "1") (pinfunction "1_1") (pintype "passive"))
      (node (ref "C25") (pin "1") (pinfunction "1_1") (pintype "passive"))
      (node (ref "C26") (pin "1") (pinfunction "1_1") (pintype "passive"))
      (node (ref "C27") (pin "1") (pinfunction "1_1") (pintype "passive"))
      (node (ref "C28") (pin "1") (pinfunction "1_1") (pintype "passive"))
      (node (ref "C29") (pin "1") (pinfunction "1_1") (pintype "passive"))
      (node (ref "C30") (pin "1") (pinfunction "1_1") (pintype "passive"))
      (node (ref "C31") (pin "1") (pinfunction "1_1") (pintype "passive"))
      (node (ref "C32") (pin "1") (pinfunction "1_1") (pintype "passive"))
      (node (ref "C33") (pin "1") (pinfunction "1_1") (pintype "passive"))
      (node (ref "C34") (pin "1") (pinfunction "1_1") (pintype "passive"))
      (node (ref "C35") (pin "1") (pinfunction "1_1") (pintype "passive"))
      (node (ref "C36") (pin "1") (pinfunction "1_1") (pintype "passive"))
      (node (ref "C37") (pin "1") (pinfunction "1_1") (pintype "passive"))
      (node (ref "C38") (pin "1") (pinfunction "1_1") (pintype "passive"))
      (node (ref "C39") (pin "1") (pinfunction "1_1") (pintype "passive"))
      (node (ref "C4") (pin "1") (pinfunction "1_1") (pintype "passive"))
      (node (ref "C40") (pin "1") (pinfunction "1_1") (pintype "passive"))
      (node (ref "C41") (pin "1") (pinfunction "1_1") (pintype "passive"))
      (node (ref "C42") (pin "1") (pinfunction "1_1") (pintype "passive"))
      (node (ref "C43") (pin "1") (pinfunction "1_1") (pintype "passive"))
      (node (ref "C44") (pin "1") (pinfunction "1_1") (pintype "passive"))
      (node (ref "C45") (pin "1") (pinfunction "1_1") (pintype "passive"))
      (node (ref "C46") (pin "1") (pinfunction "1_1") (pintype "passive"))
      (node (ref "C47") (pin "1") (pinfunction "1_1") (pintype "passive"))
      (node (ref "C48") (pin "1") (pinfunction "1_1") (pintype "passive"))
      (node (ref "C49") (pin "1") (pinfunction "1_1") (pintype "passive"))
      (node (ref "C5") (pin "1") (pinfunction "1_1") (pintype "passive"))
      (node (ref "D4") (pin "2") (pinfunction "2_2") (pintype "passive"))
      (node (ref "IC1") (pin "10") (pinfunction "~{SCLR}_10") (pintype "input"))
      (node (ref "IC1") (pin "16") (pinfunction "VCC_16") (pintype "power_in"))
      (node (ref "IC10") (pin "10") (pinfunction "~{SCLR}_10") (pintype "input"))
      (node (ref "IC10") (pin "16") (pinfunction "VCC_16") (pintype "power_in"))
      (node (ref "IC11") (pin "10") (pinfunction "~{SCLR}_10") (pintype "input"))
      (node (ref "IC11") (pin "16") (pinfunction "VCC_16") (pintype "power_in"))
      (node (ref "IC12") (pin "24") (pinfunction "VCC_24") (pintype "bidirectional"))
      (node (ref "IC13") (pin "24") (pinfunction "VCC_24") (pintype "bidirectional"))
      (node (ref "IC14") (pin "24") (pinfunction "VCC_24") (pintype "bidirectional"))
      (node (ref "IC15") (pin "24") (pinfunction "VCC_24") (pintype "bidirectional"))
      (node (ref "IC16") (pin "10") (pinfunction "~{SCLR}_10") (pintype "input"))
      (node (ref "IC16") (pin "16") (pinfunction "VCC_16") (pintype "power_in"))
      (node (ref "IC17") (pin "24") (pinfunction "VCC_24") (pintype "bidirectional"))
      (node (ref "IC2") (pin "24") (pinfunction "VCC_24") (pintype "bidirectional"))
      (node (ref "IC3") (pin "10") (pinfunction "~{SCLR}_10") (pintype "input"))
      (node (ref "IC3") (pin "16") (pinfunction "VCC_16") (pintype "power_in"))
      (node (ref "IC4") (pin "10") (pinfunction "~{SCLR}_10") (pintype "input"))
      (node (ref "IC4") (pin "16") (pinfunction "VCC_16") (pintype "power_in"))
      (node (ref "IC5") (pin "10") (pinfunction "~{SCLR}_10") (pintype "input"))
      (node (ref "IC5") (pin "16") (pinfunction "VCC_16") (pintype "power_in"))
      (node (ref "IC6") (pin "10") (pinfunction "~{SCLR}_10") (pintype "input"))
      (node (ref "IC6") (pin "16") (pinfunction "VCC_16") (pintype "power_in"))
      (node (ref "IC7") (pin "10") (pinfunction "~{SCLR}_10") (pintype "input"))
      (node (ref "IC7") (pin "16") (pinfunction "VCC_16") (pintype "power_in"))
      (node (ref "IC8") (pin "10") (pinfunction "~{SCLR}_10") (pintype "input"))
      (node (ref "IC8") (pin "16") (pinfunction "VCC_16") (pintype "power_in"))
      (node (ref "IC9") (pin "10") (pinfunction "~{SCLR}_10") (pintype "input"))
      (node (ref "IC9") (pin "16") (pinfunction "VCC_16") (pintype "power_in"))
      (node (ref "R6") (pin "1") (pinfunction "1_1") (pintype "passive"))
      (node (ref "R8") (pin "1") (pinfunction "1_1") (pintype "passive"))
      (node (ref "U$5") (pin "1") (pinfunction "1_1") (pintype "passive"))
    )
    (net (code "3") (name "24V") (class "Default")
      (node (ref "D3") (pin "1") (pinfunction "1_1") (pintype "passive"))
      (node (ref "D8") (pin "1") (pinfunction "1_1") (pintype "passive"))
      (node (ref "J1") (pin "2") (pinfunction "2_2") (pintype "passive"))
      (node (ref "R1") (pin "2") (pinfunction "2_2") (pintype "passive"))
      (node (ref "R9") (pin "2") (pinfunction "2_2") (pintype "passive"))
    )
    (net (code "4") (name "D+") (class "Default")
      (node (ref "U$3") (pin "5") (pinfunction "D+_5") (pintype "bidirectional"))
      (node (ref "X1") (pin "3") (pinfunction "3_3") (pintype "bidirectional"))
    )
    (net (code "5") (name "D-") (class "Default")
      (node (ref "U$3") (pin "6") (pinfunction "D-_6") (pintype "bidirectional"))
      (node (ref "X1") (pin "2") (pinfunction "2_2") (pintype "bidirectional"))
    )
    (net (code "6") (name "DS") (class "Default")
      (node (ref "IC1") (pin "14") (pinfunction "SER_14") (pintype "input"))
      (node (ref "U1") (pin "37") (pinfunction "IO23_37") (pintype "bidirectional"))
    )
    (net (code "7") (name "DTR") (class "Default")
      (node (ref "T1") (pin "2") (pinfunction "S_2") (pintype "passive"))
      (node (ref "T2") (pin "1") (pinfunction "G_1") (pintype "passive"))
      (node (ref "U$3") (pin "13") (pinfunction "DTR_13") (pintype "bidirectional"))
    )
    (net (code "8") (name "EN") (class "Default")
      (node (ref "C1") (pin "1") (pinfunction "1_1") (pintype "passive"))
      (node (ref "JMPEN") (pin "1") (pinfunction "1_1") (pintype "passive"))
      (node (ref "T2") (pin "3") (pinfunction "D_3") (pintype "passive"))
    )
    (net (code "9") (name "EN_MUX_1") (class "Default")
      (node (ref "IC2") (pin "15") (pinfunction "~{E}_15") (pintype "bidirectional"))
      (node (ref "R18") (pin "1") (pinfunction "1_1") (pintype "passive"))
      (node (ref "U1") (pin "10") (pinfunction "IO25_10") (pintype "bidirectional"))
    )
    (net (code "10") (name "EN_MUX_2") (class "Default")
      (node (ref "IC12") (pin "15") (pinfunction "~{E}_15") (pintype "bidirectional"))
      (node (ref "R19") (pin "1") (pinfunction "1_1") (pintype "passive"))
      (node (ref "U1") (pin "9") (pinfunction "IO33_9") (pintype "bidirectional"))
    )
    (net (code "11") (name "EN_MUX_3") (class "Default")
      (node (ref "IC13") (pin "15") (pinfunction "~{E}_15") (pintype "bidirectional"))
      (node (ref "R20") (pin "1") (pinfunction "1_1") (pintype "passive"))
      (node (ref "U1") (pin "23") (pinfunction "IO15_23") (pintype "bidirectional"))
    )
    (net (code "12") (name "EN_MUX_4") (class "Default")
      (node (ref "IC14") (pin "15") (pinfunction "~{E}_15") (pintype "bidirectional"))
      (node (ref "R21") (pin "1") (pinfunction "1_1") (pintype "passive"))
      (node (ref "U1") (pin "24") (pinfunction "IO2_24") (pintype "bidirectional"))
    )
    (net (code "13") (name "EN_MUX_5") (class "Default")
      (node (ref "IC15") (pin "15") (pinfunction "~{E}_15") (pintype "bidirectional"))
      (node (ref "R22") (pin "1") (pinfunction "1_1") (pintype "passive"))
      (node (ref "U1") (pin "26") (pinfunction "IO4_26") (pintype "bidirectional"))
    )
    (net (code "14") (name "EN_MUX_6") (class "Default")
      (node (ref "IC17") (pin "15") (pinfunction "~{E}_15") (pintype "bidirectional"))
      (node (ref "R23") (pin "1") (pinfunction "1_1") (pintype "passive"))
      (node (ref "U1") (pin "12") (pinfunction "IO27_12") (pintype "bidirectional"))
    )
    (net (code "15") (name "ESPLED") (class "Default")
      (node (ref "R24") (pin "1") (pinfunction "1_1") (pintype "passive"))
      (node (ref "U1") (pin "27") (pinfunction "IO16_27") (pintype "bidirectional"))
    )
    (net (code "16") (name "ESP_EN") (class "Default")
      (node (ref "JMPEN") (pin "2") (pinfunction "2_2") (pintype "passive"))
      (node (ref "PIN") (pin "3") (pinfunction "3_3") (pintype "passive"))
      (node (ref "U1") (pin "3") (pinfunction "EN_3") (pintype "input"))
    )
    (net (code "17") (name "ESP_IO") (class "Default")
      (node (ref "JMPIO") (pin "2") (pinfunction "2_2") (pintype "passive"))
      (node (ref "PIN") (pin "4") (pinfunction "4_4") (pintype "passive"))
      (node (ref "U1") (pin "25") (pinfunction "IO0_25") (pintype "bidirectional"))
    )
    (net (code "18") (name "ESP_RX") (class "Default")
      (node (ref "LED3") (pin "C") (pinfunction "C_C") (pintype "passive"))
      (node (ref "PIN") (pin "5") (pinfunction "5_5") (pintype "passive"))
      (node (ref "U$3") (pin "2") (pinfunction "TX_2") (pintype "bidirectional"))
      (node (ref "U1") (pin "34") (pinfunction "RXD0_34") (pintype "bidirectional"))
    )
    (net (code "19") (name "ESP_TX") (class "Default")
      (node (ref "LED4") (pin "C") (pinfunction "C_C") (pintype "passive"))
      (node (ref "PIN") (pin "6") (pinfunction "6_6") (pintype "passive"))
      (node (ref "U$3") (pin "3") (pinfunction "RX_3") (pintype "bidirectional"))
      (node (ref "U1") (pin "35") (pinfunction "TXD0_35") (pintype "bidirectional"))
    )
    (net (code "20") (name "GND") (class "Default")
      (node (ref "C1") (pin "2") (pinfunction "2_2") (pintype "passive"))
      (node (ref "C10") (pin "2") (pinfunction "2_2") (pintype "passive"))
      (node (ref "C11") (pin "2") (pinfunction "2_2") (pintype "passive"))
      (node (ref "C14") (pin "1") (pinfunction "1_1") (pintype "passive"))
      (node (ref "C16") (pin "2") (pinfunction "2_2") (pintype "passive"))
      (node (ref "C17") (pin "2") (pinfunction "2_2") (pintype "passive"))
      (node (ref "C18") (pin "2") (pinfunction "2_2") (pintype "passive"))
      (node (ref "C19") (pin "2") (pinfunction "2_2") (pintype "passive"))
      (node (ref "C2") (pin "2") (pinfunction "2_2") (pintype "passive"))
      (node (ref "C20") (pin "2") (pinfunction "2_2") (pintype "passive"))
      (node (ref "C21") (pin "2") (pinfunction "2_2") (pintype "passive"))
      (node (ref "C22") (pin "2") (pinfunction "2_2") (pintype "passive"))
      (node (ref "C23") (pin "2") (pinfunction "2_2") (pintype "passive"))
      (node (ref "C24") (pin "2") (pinfunction "2_2") (pintype "passive"))
      (node (ref "C25") (pin "2") (pinfunction "2_2") (pintype "passive"))
      (node (ref "C26") (pin "2") (pinfunction "2_2") (pintype "passive"))
      (node (ref "C27") (pin "2") (pinfunction "2_2") (pintype "passive"))
      (node (ref "C28") (pin "2") (pinfunction "2_2") (pintype "passive"))
      (node (ref "C29") (pin "2") (pinfunction "2_2") (pintype "passive"))
      (node (ref "C3") (pin "2") (pinfunction "2_2") (pintype "passive"))
      (node (ref "C30") (pin "2") (pinfunction "2_2") (pintype "passive"))
      (node (ref "C31") (pin "2") (pinfunction "2_2") (pintype "passive"))
      (node (ref "C32") (pin "2") (pinfunction "2_2") (pintype "passive"))
      (node (ref "C33") (pin "2") (pinfunction "2_2") (pintype "passive"))
      (node (ref "C34") (pin "2") (pinfunction "2_2") (pintype "passive"))
      (node (ref "C35") (pin "2") (pinfunction "2_2") (pintype "passive"))
      (node (ref "C36") (pin "2") (pinfunction "2_2") (pintype "passive"))
      (node (ref "C37") (pin "2") (pinfunction "2_2") (pintype "passive"))
      (node (ref "C38") (pin "2") (pinfunction "2_2") (pintype "passive"))
      (node (ref "C39") (pin "2") (pinfunction "2_2") (pintype "passive"))
      (node (ref "C4") (pin "2") (pinfunction "2_2") (pintype "passive"))
      (node (ref "C40") (pin "2") (pinfunction "2_2") (pintype "passive"))
      (node (ref "C41") (pin "2") (pinfunction "2_2") (pintype "passive"))
      (node (ref "C42") (pin "2") (pinfunction "2_2") (pintype "passive"))
      (node (ref "C43") (pin "2") (pinfunction "2_2") (pintype "passive"))
      (node (ref "C44") (pin "2") (pinfunction "2_2") (pintype "passive"))
      (node (ref "C45") (pin "2") (pinfunction "2_2") (pintype "passive"))
      (node (ref "C46") (pin "2") (pinfunction "2_2") (pintype "passive"))
      (node (ref "C47") (pin "2") (pinfunction "2_2") (pintype "passive"))
      (node (ref "C48") (pin "2") (pinfunction "2_2") (pintype "passive"))
      (node (ref "C49") (pin "2") (pinfunction "2_2") (pintype "passive"))
      (node (ref "C5") (pin "2") (pinfunction "2_2") (pintype "passive"))
      (node (ref "C50") (pin "2") (pinfunction "2_2") (pintype "passive"))
      (node (ref "C51") (pin "2") (pinfunction "2_2") (pintype "passive"))
      (node (ref "C8") (pin "1") (pinfunction "1_1") (pintype "passive"))
      (node (ref "D1") (pin "A") (pinfunction "A_A") (pintype "passive"))
      (node (ref "D19") (pin "1") (pinfunction "1_1") (pintype "passive"))
      (node (ref "D2") (pin "A") (pinfunction "A_A") (pintype "passive"))
      (node (ref "D3") (pin "2") (pinfunction "2_2") (pintype "passive"))
      (node (ref "D4") (pin "1") (pinfunction "1_1") (pintype "passive"))
      (node (ref "D8") (pin "2") (pinfunction "2_2") (pintype "passive"))
      (node (ref "IC1") (pin "13") (pinfunction "~{OE}_13") (pintype "input"))
      (node (ref "IC1") (pin "8") (pinfunction "GND_8") (pintype "power_in"))
      (node (ref "IC10") (pin "13") (pinfunction "~{OE}_13") (pintype "input"))
      (node (ref "IC10") (pin "8") (pinfunction "GND_8") (pintype "power_in"))
      (node (ref "IC11") (pin "13") (pinfunction "~{OE}_13") (pintype "input"))
      (node (ref "IC11") (pin "8") (pinfunction "GND_8") (pintype "power_in"))
      (node (ref "IC12") (pin "12") (pinfunction "GND_12") (pintype "bidirectional"))
      (node (ref "IC13") (pin "12") (pinfunction "GND_12") (pintype "bidirectional"))
      (node (ref "IC14") (pin "12") (pinfunction "GND_12") (pintype "bidirectional"))
      (node (ref "IC15") (pin "12") (pinfunction "GND_12") (pintype "bidirectional"))
      (node (ref "IC16") (pin "13") (pinfunction "~{OE}_13") (pintype "input"))
      (node (ref "IC16") (pin "8") (pinfunction "GND_8") (pintype "power_in"))
      (node (ref "IC17") (pin "12") (pinfunction "GND_12") (pintype "bidirectional"))
      (node (ref "IC2") (pin "12") (pinfunction "GND_12") (pintype "bidirectional"))
      (node (ref "IC3") (pin "13") (pinfunction "~{OE}_13") (pintype "input"))
      (node (ref "IC3") (pin "8") (pinfunction "GND_8") (pintype "power_in"))
      (node (ref "IC4") (pin "13") (pinfunction "~{OE}_13") (pintype "input"))
      (node (ref "IC4") (pin "8") (pinfunction "GND_8") (pintype "power_in"))
      (node (ref "IC5") (pin "13") (pinfunction "~{OE}_13") (pintype "input"))
      (node (ref "IC5") (pin "8") (pinfunction "GND_8") (pintype "power_in"))
      (node (ref "IC6") (pin "13") (pinfunction "~{OE}_13") (pintype "input"))
      (node (ref "IC6") (pin "8") (pinfunction "GND_8") (pintype "power_in"))
      (node (ref "IC7") (pin "13") (pinfunction "~{OE}_13") (pintype "input"))
      (node (ref "IC7") (pin "8") (pinfunction "GND_8") (pintype "power_in"))
      (node (ref "IC8") (pin "13") (pinfunction "~{OE}_13") (pintype "input"))
      (node (ref "IC8") (pin "8") (pinfunction "GND_8") (pintype "power_in"))
      (node (ref "IC9") (pin "13") (pinfunction "~{OE}_13") (pintype "input"))
      (node (ref "IC9") (pin "8") (pinfunction "GND_8") (pintype "power_in"))
      (node (ref "J1") (pin "1") (pinfunction "1_1") (pintype "passive"))
      (node (ref "JMPIO") (pin "3") (pinfunction "3_3") (pintype "passive"))
      (node (ref "LED1") (pin "C") (pinfunction "C_C") (pintype "passive"))
      (node (ref "LED2") (pin "C") (pinfunction "C_C") (pintype "passive"))
      (node (ref "LED5") (pin "C") (pinfunction "C_C") (pintype "passive"))
      (node (ref "LED6") (pin "C") (pinfunction "C_C") (pintype "passive"))
      (node (ref "PIN") (pin "2") (pinfunction "2_2") (pintype "passive"))
      (node (ref "R11") (pin "1") (pinfunction "1_1") (pintype "passive"))
      (node (ref "R12") (pin "1") (pinfunction "1_1") (pintype "passive"))
      (node (ref "R13") (pin "1") (pinfunction "1_1") (pintype "passive"))
      (node (ref "R18") (pin "2") (pinfunction "2_2") (pintype "passive"))
      (node (ref "R19") (pin "2") (pinfunction "2_2") (pintype "passive"))
      (node (ref "R20") (pin "2") (pinfunction "2_2") (pintype "passive"))
      (node (ref "R21") (pin "2") (pinfunction "2_2") (pintype "passive"))
      (node (ref "R22") (pin "2") (pinfunction "2_2") (pintype "passive"))
      (node (ref "R23") (pin "2") (pinfunction "2_2") (pintype "passive"))
      (node (ref "R3") (pin "1") (pinfunction "1_1") (pintype "passive"))
      (node (ref "R4") (pin "1") (pinfunction "1_1") (pintype "passive"))
      (node (ref "R41") (pin "1") (pinfunction "1_1") (pintype "passive"))
      (node (ref "R5") (pin "1") (pinfunction "1_1") (pintype "passive"))
      (node (ref "R7") (pin "1") (pinfunction "1_1") (pintype "passive"))
      (node (ref "U$3") (pin "1") (pinfunction "GND_1") (pintype "bidirectional"))
      (node (ref "U1") (pin "1") (pinfunction "GND_1") (pintype "power_in"))
      (node (ref "U1") (pin "15") (pinfunction "GND_15") (pintype "power_in"))
      (node (ref "U1") (pin "38") (pinfunction "GND_38") (pintype "power_in"))
      (node (ref "U1") (pin "39_1") (pinfunction "GND_39_1") (pintype "power_in"))
      (node (ref "U1") (pin "39_10") (pinfunction "GND_39_10") (pintype "power_in"))
      (node (ref "U1") (pin "39_11") (pinfunction "GND_39_11") (pintype "power_in"))
      (node (ref "U1") (pin "39_12") (pinfunction "GND_39_12") (pintype "power_in"))
      (node (ref "U1") (pin "39_13") (pinfunction "GND_39_13") (pintype "power_in"))
      (node (ref "U1") (pin "39_14") (pinfunction "GND_39_14") (pintype "power_in"))
      (node (ref "U1") (pin "39_15") (pinfunction "GND_39_15") (pintype "power_in"))
      (node (ref "U1") (pin "39_16") (pinfunction "GND_39_16") (pintype "power_in"))
      (node (ref "U1") (pin "39_17") (pinfunction "GND_39_17") (pintype "power_in"))
      (node (ref "U1") (pin "39_18") (pinfunction "GND_39_18") (pintype "power_in"))
      (node (ref "U1") (pin "39_19") (pinfunction "GND_39_19") (pintype "power_in"))
      (node (ref "U1") (pin "39_2") (pinfunction "GND_39_2") (pintype "power_in"))
      (node (ref "U1") (pin "39_20") (pinfunction "GND_39_20") (pintype "power_in"))
      (node (ref "U1") (pin "39_21") (pinfunction "GND_39_21") (pintype "power_in"))
      (node (ref "U1") (pin "39_3") (pinfunction "GND_39_3") (pintype "power_in"))
      (node (ref "U1") (pin "39_4") (pinfunction "GND_39_4") (pintype "power_in"))
      (node (ref "U1") (pin "39_5") (pinfunction "GND_39_5") (pintype "power_in"))
      (node (ref "U1") (pin "39_6") (pinfunction "GND_39_6") (pintype "power_in"))
      (node (ref "U1") (pin "39_7") (pinfunction "GND_39_7") (pintype "power_in"))
      (node (ref "U1") (pin "39_8") (pinfunction "GND_39_8") (pintype "power_in"))
      (node (ref "U1") (pin "39_9") (pinfunction "GND_39_9") (pintype "power_in"))
      (node (ref "U2") (pin "5") (pinfunction "GND_5") (pintype "power_in"))
      (node (ref "U2") (pin "9") (pinfunction "EP_9") (pintype "power_in"))
      (node (ref "U3") (pin "5") (pinfunction "GND_5") (pintype "power_in"))
      (node (ref "U3") (pin "9") (pinfunction "EP_9") (pintype "power_in"))
      (node (ref "X1") (pin "4") (pinfunction "4_4") (pintype "bidirectional"))
    )
    (net (code "21") (name "I1") (class "Default")
      (node (ref "IC2") (pin "9") (pinfunction "Y0_9") (pintype "bidirectional"))
      (node (ref "P3") (pin "13") (pinfunction "13_13") (pintype "passive"))
    )
    (net (code "22") (name "I2") (class "Default")
      (node (ref "IC2") (pin "8") (pinfunction "Y1_8") (pintype "bidirectional"))
      (node (ref "P3") (pin "12") (pinfunction "12_12") (pintype "passive"))
    )
    (net (code "23") (name "I3") (class "Default")
      (node (ref "IC2") (pin "7") (pinfunction "Y2_7") (pintype "bidirectional"))
      (node (ref "P3") (pin "11") (pinfunction "11_11") (pintype "passive"))
    )
    (net (code "24") (name "I4") (class "Default")
      (node (ref "IC2") (pin "6") (pinfunction "Y3_6") (pintype "bidirectional"))
      (node (ref "P3") (pin "10") (pinfunction "10_10") (pintype "passive"))
    )
    (net (code "25") (name "I5") (class "Default")
      (node (ref "IC2") (pin "5") (pinfunction "Y4_5") (pintype "bidirectional"))
      (node (ref "P3") (pin "9") (pinfunction "9_9") (pintype "passive"))
    )
    (net (code "26") (name "I6") (class "Default")
      (node (ref "IC2") (pin "4") (pinfunction "Y5_4") (pintype "bidirectional"))
      (node (ref "P3") (pin "8") (pinfunction "8_8") (pintype "passive"))
    )
    (net (code "27") (name "I7") (class "Default")
      (node (ref "IC2") (pin "3") (pinfunction "Y6_3") (pintype "bidirectional"))
      (node (ref "P3") (pin "7") (pinfunction "7_7") (pintype "passive"))
    )
    (net (code "28") (name "I8") (class "Default")
      (node (ref "IC2") (pin "2") (pinfunction "Y7_2") (pintype "bidirectional"))
      (node (ref "P3") (pin "6") (pinfunction "6_6") (pintype "passive"))
    )
    (net (code "29") (name "I9") (class "Default")
      (node (ref "IC2") (pin "23") (pinfunction "Y8_23") (pintype "bidirectional"))
      (node (ref "P3") (pin "5") (pinfunction "5_5") (pintype "passive"))
    )
    (net (code "30") (name "I10") (class "Default")
      (node (ref "IC2") (pin "22") (pinfunction "Y9_22") (pintype "bidirectional"))
      (node (ref "P3") (pin "4") (pinfunction "4_4") (pintype "passive"))
    )
    (net (code "31") (name "I11") (class "Default")
      (node (ref "IC2") (pin "21") (pinfunction "Y10_21") (pintype "bidirectional"))
      (node (ref "P3") (pin "3") (pinfunction "3_3") (pintype "passive"))
    )
    (net (code "32") (name "I12") (class "Default")
      (node (ref "IC2") (pin "20") (pinfunction "Y11_20") (pintype "bidirectional"))
      (node (ref "P3") (pin "2") (pinfunction "2_2") (pintype "passive"))
    )
    (net (code "33") (name "I13") (class "Default")
      (node (ref "IC2") (pin "19") (pinfunction "Y12_19") (pintype "bidirectional"))
      (node (ref "P3") (pin "1") (pinfunction "1_1") (pintype "passive"))
    )
    (net (code "34") (name "I14") (class "Default")
      (node (ref "IC2") (pin "18") (pinfunction "Y13_18") (pintype "bidirectional"))
      (node (ref "P3") (pin "26") (pinfunction "26_26") (pintype "passive"))
    )
    (net (code "35") (name "I15") (class "Default")
      (node (ref "IC2") (pin "17") (pinfunction "Y14_17") (pintype "bidirectional"))
      (node (ref "P3") (pin "25") (pinfunction "25_25") (pintype "passive"))
    )
    (net (code "36") (name "I16") (class "Default")
      (node (ref "IC2") (pin "16") (pinfunction "Y15_16") (pintype "bidirectional"))
      (node (ref "P3") (pin "24") (pinfunction "24_24") (pintype "passive"))
    )
    (net (code "37") (name "I17") (class "Default")
      (node (ref "IC12") (pin "9") (pinfunction "Y0_9") (pintype "bidirectional"))
      (node (ref "P3") (pin "23") (pinfunction "23_23") (pintype "passive"))
    )
    (net (code "38") (name "I18") (class "Default")
      (node (ref "IC12") (pin "8") (pinfunction "Y1_8") (pintype "bidirectional"))
      (node (ref "P3") (pin "22") (pinfunction "22_22") (pintype "passive"))
    )
    (net (code "39") (name "I19") (class "Default")
      (node (ref "IC12") (pin "7") (pinfunction "Y2_7") (pintype "bidirectional"))
      (node (ref "P3") (pin "21") (pinfunction "21_21") (pintype "passive"))
    )
    (net (code "40") (name "I20") (class "Default")
      (node (ref "IC12") (pin "6") (pinfunction "Y3_6") (pintype "bidirectional"))
      (node (ref "P3") (pin "20") (pinfunction "20_20") (pintype "passive"))
    )
    (net (code "41") (name "I21") (class "Default")
      (node (ref "IC12") (pin "5") (pinfunction "Y4_5") (pintype "bidirectional"))
      (node (ref "P3") (pin "19") (pinfunction "19_19") (pintype "passive"))
    )
    (net (code "42") (name "I22") (class "Default")
      (node (ref "IC12") (pin "4") (pinfunction "Y5_4") (pintype "bidirectional"))
      (node (ref "P3") (pin "18") (pinfunction "18_18") (pintype "passive"))
    )
    (net (code "43") (name "I23") (class "Default")
      (node (ref "IC12") (pin "3") (pinfunction "Y6_3") (pintype "bidirectional"))
      (node (ref "P3") (pin "17") (pinfunction "17_17") (pintype "passive"))
    )
    (net (code "44") (name "I24") (class "Default")
      (node (ref "IC12") (pin "2") (pinfunction "Y7_2") (pintype "bidirectional"))
      (node (ref "P3") (pin "16") (pinfunction "16_16") (pintype "passive"))
    )
    (net (code "45") (name "I25") (class "Default")
      (node (ref "IC12") (pin "23") (pinfunction "Y8_23") (pintype "bidirectional"))
      (node (ref "P3") (pin "15") (pinfunction "15_15") (pintype "passive"))
    )
    (net (code "46") (name "I26") (class "Default")
      (node (ref "IC12") (pin "22") (pinfunction "Y9_22") (pintype "bidirectional"))
      (node (ref "P3") (pin "14") (pinfunction "14_14") (pintype "passive"))
    )
    (net (code "47") (name "I27") (class "Default")
      (node (ref "IC12") (pin "21") (pinfunction "Y10_21") (pintype "bidirectional"))
      (node (ref "P4") (pin "13") (pinfunction "13_13") (pintype "passive"))
    )
    (net (code "48") (name "I28") (class "Default")
      (node (ref "IC12") (pin "20") (pinfunction "Y11_20") (pintype "bidirectional"))
      (node (ref "P4") (pin "12") (pinfunction "12_12") (pintype "passive"))
    )
    (net (code "49") (name "I29") (class "Default")
      (node (ref "IC12") (pin "19") (pinfunction "Y12_19") (pintype "bidirectional"))
      (node (ref "P4") (pin "11") (pinfunction "11_11") (pintype "passive"))
    )
    (net (code "50") (name "I30") (class "Default")
      (node (ref "IC12") (pin "18") (pinfunction "Y13_18") (pintype "bidirectional"))
      (node (ref "P4") (pin "10") (pinfunction "10_10") (pintype "passive"))
    )
    (net (code "51") (name "I31") (class "Default")
      (node (ref "IC12") (pin "17") (pinfunction "Y14_17") (pintype "bidirectional"))
      (node (ref "P4") (pin "9") (pinfunction "9_9") (pintype "passive"))
    )
    (net (code "52") (name "I32") (class "Default")
      (node (ref "IC12") (pin "16") (pinfunction "Y15_16") (pintype "bidirectional"))
      (node (ref "P4") (pin "8") (pinfunction "8_8") (pintype "passive"))
    )
    (net (code "53") (name "I33") (class "Default")
      (node (ref "IC13") (pin "9") (pinfunction "Y0_9") (pintype "bidirectional"))
      (node (ref "P4") (pin "7") (pinfunction "7_7") (pintype "passive"))
    )
    (net (code "54") (name "I34") (class "Default")
      (node (ref "IC13") (pin "8") (pinfunction "Y1_8") (pintype "bidirectional"))
      (node (ref "P4") (pin "6") (pinfunction "6_6") (pintype "passive"))
    )
    (net (code "55") (name "I35") (class "Default")
      (node (ref "IC13") (pin "7") (pinfunction "Y2_7") (pintype "bidirectional"))
      (node (ref "P4") (pin "5") (pinfunction "5_5") (pintype "passive"))
    )
    (net (code "56") (name "I36") (class "Default")
      (node (ref "IC13") (pin "6") (pinfunction "Y3_6") (pintype "bidirectional"))
      (node (ref "P4") (pin "4") (pinfunction "4_4") (pintype "passive"))
    )
    (net (code "57") (name "I37") (class "Default")
      (node (ref "IC13") (pin "5") (pinfunction "Y4_5") (pintype "bidirectional"))
      (node (ref "P4") (pin "3") (pinfunction "3_3") (pintype "passive"))
    )
    (net (code "58") (name "I38") (class "Default")
      (node (ref "IC13") (pin "4") (pinfunction "Y5_4") (pintype "bidirectional"))
      (node (ref "P4") (pin "2") (pinfunction "2_2") (pintype "passive"))
    )
    (net (code "59") (name "I39") (class "Default")
      (node (ref "IC13") (pin "3") (pinfunction "Y6_3") (pintype "bidirectional"))
      (node (ref "P4") (pin "1") (pinfunction "1_1") (pintype "passive"))
    )
    (net (code "60") (name "I40") (class "Default")
      (node (ref "IC13") (pin "2") (pinfunction "Y7_2") (pintype "bidirectional"))
      (node (ref "P4") (pin "26") (pinfunction "26_26") (pintype "passive"))
    )
    (net (code "61") (name "I41") (class "Default")
      (node (ref "IC13") (pin "23") (pinfunction "Y8_23") (pintype "bidirectional"))
      (node (ref "P4") (pin "25") (pinfunction "25_25") (pintype "passive"))
    )
    (net (code "62") (name "I42") (class "Default")
      (node (ref "IC13") (pin "22") (pinfunction "Y9_22") (pintype "bidirectional"))
      (node (ref "P4") (pin "24") (pinfunction "24_24") (pintype "passive"))
    )
    (net (code "63") (name "I43") (class "Default")
      (node (ref "IC13") (pin "21") (pinfunction "Y10_21") (pintype "bidirectional"))
      (node (ref "P4") (pin "23") (pinfunction "23_23") (pintype "passive"))
    )
    (net (code "64") (name "I44") (class "Default")
      (node (ref "IC13") (pin "20") (pinfunction "Y11_20") (pintype "bidirectional"))
      (node (ref "P4") (pin "22") (pinfunction "22_22") (pintype "passive"))
    )
    (net (code "65") (name "I45") (class "Default")
      (node (ref "IC13") (pin "19") (pinfunction "Y12_19") (pintype "bidirectional"))
      (node (ref "P4") (pin "21") (pinfunction "21_21") (pintype "passive"))
    )
    (net (code "66") (name "I46") (class "Default")
      (node (ref "IC13") (pin "18") (pinfunction "Y13_18") (pintype "bidirectional"))
      (node (ref "P4") (pin "20") (pinfunction "20_20") (pintype "passive"))
    )
    (net (code "67") (name "I47") (class "Default")
      (node (ref "IC13") (pin "17") (pinfunction "Y14_17") (pintype "bidirectional"))
      (node (ref "P4") (pin "19") (pinfunction "19_19") (pintype "passive"))
    )
    (net (code "68") (name "I48") (class "Default")
      (node (ref "IC13") (pin "16") (pinfunction "Y15_16") (pintype "bidirectional"))
      (node (ref "P4") (pin "18") (pinfunction "18_18") (pintype "passive"))
    )
    (net (code "69") (name "I49") (class "Default")
      (node (ref "IC14") (pin "9") (pinfunction "Y0_9") (pintype "bidirectional"))
      (node (ref "P4") (pin "17") (pinfunction "17_17") (pintype "passive"))
    )
    (net (code "70") (name "I50") (class "Default")
      (node (ref "IC14") (pin "8") (pinfunction "Y1_8") (pintype "bidirectional"))
      (node (ref "P4") (pin "16") (pinfunction "16_16") (pintype "passive"))
    )
    (net (code "71") (name "I51") (class "Default")
      (node (ref "IC14") (pin "7") (pinfunction "Y2_7") (pintype "bidirectional"))
      (node (ref "P4") (pin "15") (pinfunction "15_15") (pintype "passive"))
    )
    (net (code "72") (name "I52") (class "Default")
      (node (ref "IC14") (pin "6") (pinfunction "Y3_6") (pintype "bidirectional"))
      (node (ref "P4") (pin "14") (pinfunction "14_14") (pintype "passive"))
    )
    (net (code "73") (name "I53") (class "Default")
      (node (ref "IC14") (pin "5") (pinfunction "Y4_5") (pintype "bidirectional"))
      (node (ref "J2") (pin "24") (pinfunction "24_24") (pintype "passive"))
    )
    (net (code "74") (name "I54") (class "Default")
      (node (ref "IC14") (pin "4") (pinfunction "Y5_4") (pintype "bidirectional"))
      (node (ref "J2") (pin "23") (pinfunction "23_23") (pintype "passive"))
    )
    (net (code "75") (name "I55") (class "Default")
      (node (ref "IC14") (pin "3") (pinfunction "Y6_3") (pintype "bidirectional"))
      (node (ref "J2") (pin "22") (pinfunction "22_22") (pintype "passive"))
    )
    (net (code "76") (name "I56") (class "Default")
      (node (ref "IC14") (pin "2") (pinfunction "Y7_2") (pintype "bidirectional"))
      (node (ref "J2") (pin "21") (pinfunction "21_21") (pintype "passive"))
    )
    (net (code "77") (name "I57") (class "Default")
      (node (ref "IC14") (pin "23") (pinfunction "Y8_23") (pintype "bidirectional"))
      (node (ref "J2") (pin "20") (pinfunction "20_20") (pintype "passive"))
    )
    (net (code "78") (name "I58") (class "Default")
      (node (ref "IC14") (pin "22") (pinfunction "Y9_22") (pintype "bidirectional"))
      (node (ref "J2") (pin "19") (pinfunction "19_19") (pintype "passive"))
    )
    (net (code "79") (name "I59") (class "Default")
      (node (ref "IC14") (pin "21") (pinfunction "Y10_21") (pintype "bidirectional"))
      (node (ref "J2") (pin "18") (pinfunction "18_18") (pintype "passive"))
    )
    (net (code "80") (name "I60") (class "Default")
      (node (ref "IC14") (pin "20") (pinfunction "Y11_20") (pintype "bidirectional"))
      (node (ref "J2") (pin "17") (pinfunction "17_17") (pintype "passive"))
    )
    (net (code "81") (name "I61") (class "Default")
      (node (ref "IC14") (pin "19") (pinfunction "Y12_19") (pintype "bidirectional"))
      (node (ref "J2") (pin "16") (pinfunction "16_16") (pintype "passive"))
    )
    (net (code "82") (name "I62") (class "Default")
      (node (ref "IC14") (pin "18") (pinfunction "Y13_18") (pintype "bidirectional"))
      (node (ref "J2") (pin "15") (pinfunction "15_15") (pintype "passive"))
    )
    (net (code "83") (name "I63") (class "Default")
      (node (ref "IC14") (pin "17") (pinfunction "Y14_17") (pintype "bidirectional"))
      (node (ref "J2") (pin "14") (pinfunction "14_14") (pintype "passive"))
    )
    (net (code "84") (name "I64") (class "Default")
      (node (ref "IC14") (pin "16") (pinfunction "Y15_16") (pintype "bidirectional"))
      (node (ref "J2") (pin "13") (pinfunction "13_13") (pintype "passive"))
    )
    (net (code "85") (name "I65") (class "Default")
      (node (ref "IC15") (pin "9") (pinfunction "Y0_9") (pintype "bidirectional"))
      (node (ref "J2") (pin "12") (pinfunction "12_12") (pintype "passive"))
    )
    (net (code "86") (name "I66") (class "Default")
      (node (ref "IC15") (pin "8") (pinfunction "Y1_8") (pintype "bidirectional"))
      (node (ref "J2") (pin "11") (pinfunction "11_11") (pintype "passive"))
    )
    (net (code "87") (name "I67") (class "Default")
      (node (ref "IC15") (pin "7") (pinfunction "Y2_7") (pintype "bidirectional"))
      (node (ref "J2") (pin "10") (pinfunction "10_10") (pintype "passive"))
    )
    (net (code "88") (name "I68") (class "Default")
      (node (ref "IC15") (pin "6") (pinfunction "Y3_6") (pintype "bidirectional"))
      (node (ref "J2") (pin "9") (pinfunction "9_9") (pintype "passive"))
    )
    (net (code "89") (name "I69") (class "Default")
      (node (ref "IC15") (pin "5") (pinfunction "Y4_5") (pintype "bidirectional"))
      (node (ref "J2") (pin "8") (pinfunction "8_8") (pintype "passive"))
    )
    (net (code "90") (name "I70") (class "Default")
      (node (ref "IC15") (pin "4") (pinfunction "Y5_4") (pintype "bidirectional"))
      (node (ref "J2") (pin "7") (pinfunction "7_7") (pintype "passive"))
    )
    (net (code "91") (name "I71") (class "Default")
      (node (ref "IC15") (pin "3") (pinfunction "Y6_3") (pintype "bidirectional"))
      (node (ref "J2") (pin "6") (pinfunction "6_6") (pintype "passive"))
    )
    (net (code "92") (name "I72") (class "Default")
      (node (ref "IC15") (pin "2") (pinfunction "Y7_2") (pintype "bidirectional"))
      (node (ref "J2") (pin "5") (pinfunction "5_5") (pintype "passive"))
    )
    (net (code "93") (name "I73") (class "Default")
      (node (ref "IC15") (pin "23") (pinfunction "Y8_23") (pintype "bidirectional"))
      (node (ref "J2") (pin "4") (pinfunction "4_4") (pintype "passive"))
    )
    (net (code "94") (name "I74") (class "Default")
      (node (ref "IC15") (pin "22") (pinfunction "Y9_22") (pintype "bidirectional"))
      (node (ref "J2") (pin "3") (pinfunction "3_3") (pintype "passive"))
    )
    (net (code "95") (name "I75") (class "Default")
      (node (ref "IC15") (pin "21") (pinfunction "Y10_21") (pintype "bidirectional"))
      (node (ref "J2") (pin "2") (pinfunction "2_2") (pintype "passive"))
    )
    (net (code "96") (name "I76") (class "Default")
      (node (ref "IC15") (pin "20") (pinfunction "Y11_20") (pintype "bidirectional"))
      (node (ref "J2") (pin "1") (pinfunction "1_1") (pintype "passive"))
    )
    (net (code "97") (name "I81") (class "Default")
      (node (ref "IC17") (pin "9") (pinfunction "Y0_9") (pintype "bidirectional"))
      (node (ref "J6") (pin "1") (pinfunction "1_1") (pintype "passive"))
    )
    (net (code "98") (name "I82") (class "Default")
      (node (ref "IC17") (pin "8") (pinfunction "Y1_8") (pintype "bidirectional"))
      (node (ref "J6") (pin "2") (pinfunction "2_2") (pintype "passive"))
    )
    (net (code "99") (name "I83") (class "Default")
      (node (ref "IC17") (pin "7") (pinfunction "Y2_7") (pintype "bidirectional"))
      (node (ref "J6") (pin "3") (pinfunction "3_3") (pintype "passive"))
    )
    (net (code "100") (name "I84") (class "Default")
      (node (ref "IC17") (pin "6") (pinfunction "Y3_6") (pintype "bidirectional"))
      (node (ref "J6") (pin "4") (pinfunction "4_4") (pintype "passive"))
    )
    (net (code "101") (name "I85") (class "Default")
      (node (ref "IC17") (pin "5") (pinfunction "Y4_5") (pintype "bidirectional"))
      (node (ref "J6") (pin "5") (pinfunction "5_5") (pintype "passive"))
    )
    (net (code "102") (name "I86") (class "Default")
      (node (ref "IC17") (pin "4") (pinfunction "Y5_4") (pintype "bidirectional"))
      (node (ref "J6") (pin "6") (pinfunction "6_6") (pintype "passive"))
    )
    (net (code "103") (name "I87") (class "Default")
      (node (ref "IC17") (pin "3") (pinfunction "Y6_3") (pintype "bidirectional"))
      (node (ref "J6") (pin "7") (pinfunction "7_7") (pintype "passive"))
    )
    (net (code "104") (name "I88") (class "Default")
      (node (ref "IC17") (pin "2") (pinfunction "Y7_2") (pintype "bidirectional"))
      (node (ref "J6") (pin "8") (pinfunction "8_8") (pintype "passive"))
    )
    (net (code "105") (name "IO") (class "Default")
      (node (ref "JMPIO") (pin "1") (pinfunction "1_1") (pintype "passive"))
      (node (ref "T1") (pin "3") (pinfunction "D_3") (pintype "passive"))
    )
    (net (code "106") (name "N$101") (class "Default")
      (node (ref "D72") (pin "C") (pinfunction "K_C") (pintype "passive"))
      (node (ref "J3") (pin "19") (pinfunction "19_19") (pintype "passive"))
      (node (ref "J5") (pin "4") (pinfunction "4_4") (pintype "passive"))
    )
    (net (code "107") (name "N$109") (class "Default")
      (node (ref "D85") (pin "C") (pinfunction "K_C") (pintype "passive"))
      (node (ref "J3") (pin "7") (pinfunction "7_7") (pintype "passive"))
      (node (ref "J5") (pin "3") (pinfunction "3_3") (pintype "passive"))
    )
    (net (code "108") (name "N$110") (class "Default")
      (node (ref "D86") (pin "C") (pinfunction "K_C") (pintype "passive"))
      (node (ref "J3") (pin "8") (pinfunction "8_8") (pintype "passive"))
      (node (ref "J5") (pin "2") (pinfunction "2_2") (pintype "passive"))
    )
    (net (code "109") (name "N$112") (class "Default")
      (node (ref "D88") (pin "C") (pinfunction "K_C") (pintype "passive"))
      (node (ref "J3") (pin "10") (pinfunction "10_10") (pintype "passive"))
      (node (ref "J5") (pin "1") (pinfunction "1_1") (pintype "passive"))
    )
    (net (code "110") (name "Net-(C6-Pad2)") (class "Default")
      (node (ref "C6") (pin "2") (pinfunction "2_2") (pintype "passive"))
      (node (ref "R12") (pin "2") (pinfunction "2_2") (pintype "passive"))
    )
    (net (code "111") (name "Net-(C12-Pad2)") (class "Default")
      (node (ref "C12") (pin "2") (pinfunction "2_2") (pintype "passive"))
      (node (ref "R4") (pin "2") (pinfunction "2_2") (pintype "passive"))
    )
    (net (code "112") (name "Net-(D5-K)") (class "Default")
      (node (ref "D5") (pin "C") (pinfunction "K_C") (pintype "passive"))
      (node (ref "J7") (pin "1") (pinfunction "1_1") (pintype "passive"))
    )
    (net (code "113") (name "Net-(D6-K)") (class "Default")
      (node (ref "D6") (pin "C") (pinfunction "K_C") (pintype "passive"))
      (node (ref "J7") (pin "2") (pinfunction "2_2") (pintype "passive"))
    )
    (net (code "114") (name "Net-(D7-K)") (class "Default")
      (node (ref "D7") (pin "C") (pinfunction "K_C") (pintype "passive"))
      (node (ref "J7") (pin "3") (pinfunction "3_3") (pintype "passive"))
    )
    (net (code "115") (name "Net-(D9-K)") (class "Default")
      (node (ref "D9") (pin "C") (pinfunction "K_C") (pintype "passive"))
      (node (ref "J7") (pin "4") (pinfunction "4_4") (pintype "passive"))
    )
    (net (code "116") (name "Net-(D10-K)") (class "Default")
      (node (ref "D10") (pin "C") (pinfunction "K_C") (pintype "passive"))
      (node (ref "J7") (pin "5") (pinfunction "5_5") (pintype "passive"))
    )
    (net (code "117") (name "Net-(D11-K)") (class "Default")
      (node (ref "D11") (pin "C") (pinfunction "K_C") (pintype "passive"))
      (node (ref "J7") (pin "6") (pinfunction "6_6") (pintype "passive"))
    )
    (net (code "118") (name "Net-(D12-K)") (class "Default")
      (node (ref "D12") (pin "C") (pinfunction "K_C") (pintype "passive"))
      (node (ref "J7") (pin "7") (pinfunction "7_7") (pintype "passive"))
    )
    (net (code "119") (name "Net-(D13-K)") (class "Default")
      (node (ref "D13") (pin "C") (pinfunction "K_C") (pintype "passive"))
      (node (ref "J7") (pin "8") (pinfunction "8_8") (pintype "passive"))
    )
    (net (code "120") (name "Net-(D14-K)") (class "Default")
      (node (ref "D14") (pin "C") (pinfunction "K_C") (pintype "passive"))
      (node (ref "P1") (pin "1") (pinfunction "1_1") (pintype "passive"))
    )
    (net (code "121") (name "Net-(D15-K)") (class "Default")
      (node (ref "D15") (pin "C") (pinfunction "K_C") (pintype "passive"))
      (node (ref "P1") (pin "2") (pinfunction "2_2") (pintype "passive"))
    )
    (net (code "122") (name "Net-(D16-K)") (class "Default")
      (node (ref "D16") (pin "C") (pinfunction "K_C") (pintype "passive"))
      (node (ref "P1") (pin "3") (pinfunction "3_3") (pintype "passive"))
    )
    (net (code "123") (name "Net-(D17-K)") (class "Default")
      (node (ref "D17") (pin "C") (pinfunction "K_C") (pintype "passive"))
      (node (ref "P1") (pin "4") (pinfunction "4_4") (pintype "passive"))
    )
    (net (code "124") (name "Net-(D18-K)") (class "Default")
      (node (ref "D18") (pin "C") (pinfunction "K_C") (pintype "passive"))
      (node (ref "P1") (pin "5") (pinfunction "5_5") (pintype "passive"))
    )
    (net (code "125") (name "Net-(D20-K)") (class "Default")
      (node (ref "D20") (pin "C") (pinfunction "K_C") (pintype "passive"))
      (node (ref "P1") (pin "6") (pinfunction "6_6") (pintype "passive"))
    )
    (net (code "126") (name "Net-(D21-K)") (class "Default")
      (node (ref "D21") (pin "C") (pinfunction "K_C") (pintype "passive"))
      (node (ref "P1") (pin "7") (pinfunction "7_7") (pintype "passive"))
    )
    (net (code "127") (name "Net-(D22-K)") (class "Default")
      (node (ref "D22") (pin "C") (pinfunction "K_C") (pintype "passive"))
      (node (ref "P1") (pin "8") (pinfunction "8_8") (pintype "passive"))
    )
    (net (code "128") (name "Net-(D23-K)") (class "Default")
      (node (ref "D23") (pin "C") (pinfunction "K_C") (pintype "passive"))
      (node (ref "P1") (pin "9") (pinfunction "9_9") (pintype "passive"))
    )
    (net (code "129") (name "Net-(D24-K)") (class "Default")
      (node (ref "D24") (pin "C") (pinfunction "K_C") (pintype "passive"))
      (node (ref "P1") (pin "10") (pinfunction "10_10") (pintype "passive"))
    )
    (net (code "130") (name "Net-(D25-K)") (class "Default")
      (node (ref "D25") (pin "C") (pinfunction "K_C") (pintype "passive"))
      (node (ref "P1") (pin "11") (pinfunction "11_11") (pintype "passive"))
    )
    (net (code "131") (name "Net-(D26-K)") (class "Default")
      (node (ref "D26") (pin "C") (pinfunction "K_C") (pintype "passive"))
      (node (ref "P1") (pin "12") (pinfunction "12_12") (pintype "passive"))
    )
    (net (code "132") (name "Net-(D27-K)") (class "Default")
      (node (ref "D27") (pin "C") (pinfunction "K_C") (pintype "passive"))
      (node (ref "P1") (pin "13") (pinfunction "13_13") (pintype "passive"))
    )
    (net (code "133") (name "Net-(D28-K)") (class "Default")
      (node (ref "D28") (pin "C") (pinfunction "K_C") (pintype "passive"))
      (node (ref "P1") (pin "26") (pinfunction "26_26") (pintype "passive"))
    )
    (net (code "134") (name "Net-(D29-K)") (class "Default")
      (node (ref "D29") (pin "C") (pinfunction "K_C") (pintype "passive"))
      (node (ref "P1") (pin "25") (pinfunction "25_25") (pintype "passive"))
    )
    (net (code "135") (name "Net-(D30-K)") (class "Default")
      (node (ref "D30") (pin "C") (pinfunction "K_C") (pintype "passive"))
      (node (ref "P1") (pin "24") (pinfunction "24_24") (pintype "passive"))
    )
    (net (code "136") (name "Net-(D31-K)") (class "Default")
      (node (ref "D31") (pin "C") (pinfunction "K_C") (pintype "passive"))
      (node (ref "P1") (pin "23") (pinfunction "23_23") (pintype "passive"))
    )
    (net (code "137") (name "Net-(D32-K)") (class "Default")
      (node (ref "D32") (pin "C") (pinfunction "K_C") (pintype "passive"))
      (node (ref "P1") (pin "22") (pinfunction "22_22") (pintype "passive"))
    )
    (net (code "138") (name "Net-(D33-K)") (class "Default")
      (node (ref "D33") (pin "C") (pinfunction "K_C") (pintype "passive"))
      (node (ref "P1") (pin "21") (pinfunction "21_21") (pintype "passive"))
    )
    (net (code "139") (name "Net-(D34-K)") (class "Default")
      (node (ref "D34") (pin "C") (pinfunction "K_C") (pintype "passive"))
      (node (ref "P1") (pin "20") (pinfunction "20_20") (pintype "passive"))
    )
    (net (code "140") (name "Net-(D35-K)") (class "Default")
      (node (ref "D35") (pin "C") (pinfunction "K_C") (pintype "passive"))
      (node (ref "P1") (pin "19") (pinfunction "19_19") (pintype "passive"))
    )
    (net (code "141") (name "Net-(D36-K)") (class "Default")
      (node (ref "D36") (pin "C") (pinfunction "K_C") (pintype "passive"))
      (node (ref "P1") (pin "18") (pinfunction "18_18") (pintype "passive"))
    )
    (net (code "142") (name "Net-(D37-K)") (class "Default")
      (node (ref "D37") (pin "C") (pinfunction "K_C") (pintype "passive"))
      (node (ref "P1") (pin "17") (pinfunction "17_17") (pintype "passive"))
    )
    (net (code "143") (name "Net-(D38-K)") (class "Default")
      (node (ref "D38") (pin "C") (pinfunction "K_C") (pintype "passive"))
      (node (ref "P1") (pin "16") (pinfunction "16_16") (pintype "passive"))
    )
    (net (code "144") (name "Net-(D39-K)") (class "Default")
      (node (ref "D39") (pin "C") (pinfunction "K_C") (pintype "passive"))
      (node (ref "P1") (pin "15") (pinfunction "15_15") (pintype "passive"))
    )
    (net (code "145") (name "Net-(D40-K)") (class "Default")
      (node (ref "D40") (pin "C") (pinfunction "K_C") (pintype "passive"))
      (node (ref "P1") (pin "14") (pinfunction "14_14") (pintype "passive"))
    )
    (net (code "146") (name "Net-(D41-K)") (class "Default")
      (node (ref "D41") (pin "C") (pinfunction "K_C") (pintype "passive"))
      (node (ref "P2") (pin "1") (pinfunction "1_1") (pintype "passive"))
    )
    (net (code "147") (name "Net-(D42-K)") (class "Default")
      (node (ref "D42") (pin "C") (pinfunction "K_C") (pintype "passive"))
      (node (ref "P2") (pin "2") (pinfunction "2_2") (pintype "passive"))
    )
    (net (code "148") (name "Net-(D43-K)") (class "Default")
      (node (ref "D43") (pin "C") (pinfunction "K_C") (pintype "passive"))
      (node (ref "P2") (pin "3") (pinfunction "3_3") (pintype "passive"))
    )
    (net (code "149") (name "Net-(D44-K)") (class "Default")
      (node (ref "D44") (pin "C") (pinfunction "K_C") (pintype "passive"))
      (node (ref "P2") (pin "4") (pinfunction "4_4") (pintype "passive"))
    )
    (net (code "150") (name "Net-(D45-K)") (class "Default")
      (node (ref "D45") (pin "C") (pinfunction "K_C") (pintype "passive"))
      (node (ref "P2") (pin "5") (pinfunction "5_5") (pintype "passive"))
    )
    (net (code "151") (name "Net-(D46-K)") (class "Default")
      (node (ref "D46") (pin "C") (pinfunction "K_C") (pintype "passive"))
      (node (ref "P2") (pin "6") (pinfunction "6_6") (pintype "passive"))
    )
    (net (code "152") (name "Net-(D47-K)") (class "Default")
      (node (ref "D47") (pin "C") (pinfunction "K_C") (pintype "passive"))
      (node (ref "P2") (pin "7") (pinfunction "7_7") (pintype "passive"))
    )
    (net (code "153") (name "Net-(D48-K)") (class "Default")
      (node (ref "D48") (pin "C") (pinfunction "K_C") (pintype "passive"))
      (node (ref "P2") (pin "8") (pinfunction "8_8") (pintype "passive"))
    )
    (net (code "154") (name "Net-(D49-K)") (class "Default")
      (node (ref "D49") (pin "C") (pinfunction "K_C") (pintype "passive"))
      (node (ref "P2") (pin "9") (pinfunction "9_9") (pintype "passive"))
    )
    (net (code "155") (name "Net-(D50-K)") (class "Default")
      (node (ref "D50") (pin "C") (pinfunction "K_C") (pintype "passive"))
      (node (ref "P2") (pin "10") (pinfunction "10_10") (pintype "passive"))
    )
    (net (code "156") (name "Net-(D51-K)") (class "Default")
      (node (ref "D51") (pin "C") (pinfunction "K_C") (pintype "passive"))
      (node (ref "P2") (pin "11") (pinfunction "11_11") (pintype "passive"))
    )
    (net (code "157") (name "Net-(D52-K)") (class "Default")
      (node (ref "D52") (pin "C") (pinfunction "K_C") (pintype "passive"))
      (node (ref "P2") (pin "12") (pinfunction "12_12") (pintype "passive"))
    )
    (net (code "158") (name "Net-(D53-K)") (class "Default")
      (node (ref "D53") (pin "C") (pinfunction "K_C") (pintype "passive"))
      (node (ref "P2") (pin "13") (pinfunction "13_13") (pintype "passive"))
    )
    (net (code "159") (name "Net-(D54-K)") (class "Default")
      (node (ref "D54") (pin "C") (pinfunction "K_C") (pintype "passive"))
      (node (ref "P2") (pin "26") (pinfunction "26_26") (pintype "passive"))
    )
    (net (code "160") (name "Net-(D55-K)") (class "Default")
      (node (ref "D55") (pin "C") (pinfunction "K_C") (pintype "passive"))
      (node (ref "P2") (pin "25") (pinfunction "25_25") (pintype "passive"))
    )
    (net (code "161") (name "Net-(D56-K)") (class "Default")
      (node (ref "D56") (pin "C") (pinfunction "K_C") (pintype "passive"))
      (node (ref "P2") (pin "24") (pinfunction "24_24") (pintype "passive"))
    )
    (net (code "162") (name "Net-(D57-K)") (class "Default")
      (node (ref "D57") (pin "C") (pinfunction "K_C") (pintype "passive"))
      (node (ref "P2") (pin "23") (pinfunction "23_23") (pintype "passive"))
    )
    (net (code "163") (name "Net-(D58-K)") (class "Default")
      (node (ref "D58") (pin "C") (pinfunction "K_C") (pintype "passive"))
      (node (ref "P2") (pin "22") (pinfunction "22_22") (pintype "passive"))
    )
    (net (code "164") (name "Net-(D59-K)") (class "Default")
      (node (ref "D59") (pin "C") (pinfunction "K_C") (pintype "passive"))
      (node (ref "P2") (pin "21") (pinfunction "21_21") (pintype "passive"))
    )
    (net (code "165") (name "Net-(D60-K)") (class "Default")
      (node (ref "D60") (pin "C") (pinfunction "K_C") (pintype "passive"))
      (node (ref "P2") (pin "20") (pinfunction "20_20") (pintype "passive"))
    )
    (net (code "166") (name "Net-(D61-K)") (class "Default")
      (node (ref "D61") (pin "C") (pinfunction "K_C") (pintype "passive"))
      (node (ref "P2") (pin "19") (pinfunction "19_19") (pintype "passive"))
    )
    (net (code "167") (name "Net-(D62-K)") (class "Default")
      (node (ref "D62") (pin "C") (pinfunction "K_C") (pintype "passive"))
      (node (ref "P2") (pin "18") (pinfunction "18_18") (pintype "passive"))
    )
    (net (code "168") (name "Net-(D63-K)") (class "Default")
      (node (ref "D63") (pin "C") (pinfunction "K_C") (pintype "passive"))
      (node (ref "P2") (pin "17") (pinfunction "17_17") (pintype "passive"))
    )
    (net (code "169") (name "Net-(D64-K)") (class "Default")
      (node (ref "D64") (pin "C") (pinfunction "K_C") (pintype "passive"))
      (node (ref "P2") (pin "16") (pinfunction "16_16") (pintype "passive"))
    )
    (net (code "170") (name "Net-(D65-K)") (class "Default")
      (node (ref "D65") (pin "C") (pinfunction "K_C") (pintype "passive"))
      (node (ref "P2") (pin "15") (pinfunction "15_15") (pintype "passive"))
    )
    (net (code "171") (name "Net-(D66-K)") (class "Default")
      (node (ref "D66") (pin "C") (pinfunction "K_C") (pintype "passive"))
      (node (ref "P2") (pin "14") (pinfunction "14_14") (pintype "passive"))
    )
    (net (code "172") (name "Net-(D67-K)") (class "Default")
      (node (ref "D67") (pin "C") (pinfunction "K_C") (pintype "passive"))
      (node (ref "J3") (pin "24") (pinfunction "24_24") (pintype "passive"))
    )
    (net (code "173") (name "Net-(D68-K)") (class "Default")
      (node (ref "D68") (pin "C") (pinfunction "K_C") (pintype "passive"))
      (node (ref "J3") (pin "23") (pinfunction "23_23") (pintype "passive"))
    )
    (net (code "174") (name "Net-(D69-K)") (class "Default")
      (node (ref "D69") (pin "C") (pinfunction "K_C") (pintype "passive"))
      (node (ref "J3") (pin "22") (pinfunction "22_22") (pintype "passive"))
    )
    (net (code "175") (name "Net-(D70-K)") (class "Default")
      (node (ref "D70") (pin "C") (pinfunction "K_C") (pintype "passive"))
      (node (ref "J3") (pin "21") (pinfunction "21_21") (pintype "passive"))
    )
    (net (code "176") (name "Net-(D71-K)") (class "Default")
      (node (ref "D71") (pin "C") (pinfunction "K_C") (pintype "passive"))
      (node (ref "J3") (pin "20") (pinfunction "20_20") (pintype "passive"))
    )
    (net (code "177") (name "Net-(D73-K)") (class "Default")
      (node (ref "D73") (pin "C") (pinfunction "K_C") (pintype "passive"))
      (node (ref "J3") (pin "18") (pinfunction "18_18") (pintype "passive"))
    )
    (net (code "178") (name "Net-(D74-K)") (class "Default")
      (node (ref "D74") (pin "C") (pinfunction "K_C") (pintype "passive"))
      (node (ref "J3") (pin "17") (pinfunction "17_17") (pintype "passive"))
    )
    (net (code "179") (name "Net-(D75-K)") (class "Default")
      (node (ref "D75") (pin "C") (pinfunction "K_C") (pintype "passive"))
      (node (ref "J3") (pin "16") (pinfunction "16_16") (pintype "passive"))
    )
    (net (code "180") (name "Net-(D76-K)") (class "Default")
      (node (ref "D76") (pin "C") (pinfunction "K_C") (pintype "passive"))
      (node (ref "J3") (pin "15") (pinfunction "15_15") (pintype "passive"))
    )
    (net (code "181") (name "Net-(D77-K)") (class "Default")
      (node (ref "D77") (pin "C") (pinfunction "K_C") (pintype "passive"))
      (node (ref "J3") (pin "14") (pinfunction "14_14") (pintype "passive"))
    )
    (net (code "182") (name "Net-(D78-K)") (class "Default")
      (node (ref "D78") (pin "C") (pinfunction "K_C") (pintype "passive"))
      (node (ref "J3") (pin "13") (pinfunction "13_13") (pintype "passive"))
    )
    (net (code "183") (name "Net-(D79-K)") (class "Default")
      (node (ref "D79") (pin "C") (pinfunction "K_C") (pintype "passive"))
      (node (ref "J3") (pin "1") (pinfunction "1_1") (pintype "passive"))
    )
    (net (code "184") (name "Net-(D80-K)") (class "Default")
      (node (ref "D80") (pin "C") (pinfunction "K_C") (pintype "passive"))
      (node (ref "J3") (pin "2") (pinfunction "2_2") (pintype "passive"))
    )
    (net (code "185") (name "Net-(D81-K)") (class "Default")
      (node (ref "D81") (pin "C") (pinfunction "K_C") (pintype "passive"))
      (node (ref "J3") (pin "3") (pinfunction "3_3") (pintype "passive"))
    )
    (net (code "186") (name "Net-(D82-K)") (class "Default")
      (node (ref "D82") (pin "C") (pinfunction "K_C") (pintype "passive"))
      (node (ref "J3") (pin "4") (pinfunction "4_4") (pintype "passive"))
    )
    (net (code "187") (name "Net-(D83-K)") (class "Default")
      (node (ref "D83") (pin "C") (pinfunction "K_C") (pintype "passive"))
      (node (ref "J3") (pin "5") (pinfunction "5_5") (pintype "passive"))
    )
    (net (code "188") (name "Net-(D84-K)") (class "Default")
      (node (ref "D84") (pin "C") (pinfunction "K_C") (pintype "passive"))
      (node (ref "J3") (pin "6") (pinfunction "6_6") (pintype "passive"))
    )
    (net (code "189") (name "Net-(D87-K)") (class "Default")
      (node (ref "D87") (pin "C") (pinfunction "K_C") (pintype "passive"))
      (node (ref "J3") (pin "9") (pinfunction "9_9") (pintype "passive"))
    )
    (net (code "190") (name "Net-(D89-K)") (class "Default")
      (node (ref "D89") (pin "C") (pinfunction "K_C") (pintype "passive"))
      (node (ref "J3") (pin "11") (pinfunction "11_11") (pintype "passive"))
    )
    (net (code "191") (name "Net-(D90-K)") (class "Default")
      (node (ref "D90") (pin "C") (pinfunction "K_C") (pintype "passive"))
      (node (ref "J3") (pin "12") (pinfunction "12_12") (pintype "passive"))
    )
    (net (code "192") (name "Net-(IC1-QH')") (class "Default")
      (node (ref "IC1") (pin "9") (pinfunction "QH'_9") (pintype "tri_state"))
      (node (ref "IC3") (pin "14") (pinfunction "SER_14") (pintype "input"))
    )
    (net (code "193") (name "Net-(IC3-QH')") (class "Default")
      (node (ref "IC3") (pin "9") (pinfunction "QH'_9") (pintype "tri_state"))
      (node (ref "IC4") (pin "14") (pinfunction "SER_14") (pintype "input"))
    )
    (net (code "194") (name "Net-(IC4-QH')") (class "Default")
      (node (ref "IC4") (pin "9") (pinfunction "QH'_9") (pintype "tri_state"))
      (node (ref "IC5") (pin "14") (pinfunction "SER_14") (pintype "input"))
    )
    (net (code "195") (name "Net-(IC5-QH')") (class "Default")
      (node (ref "IC5") (pin "9") (pinfunction "QH'_9") (pintype "tri_state"))
      (node (ref "IC6") (pin "14") (pinfunction "SER_14") (pintype "input"))
    )
    (net (code "196") (name "Net-(IC7-QH')") (class "Default")
      (node (ref "IC7") (pin "9") (pinfunction "QH'_9") (pintype "tri_state"))
      (node (ref "IC8") (pin "14") (pinfunction "SER_14") (pintype "input"))
    )
    (net (code "197") (name "Net-(IC8-QH')") (class "Default")
      (node (ref "IC8") (pin "9") (pinfunction "QH'_9") (pintype "tri_state"))
      (node (ref "IC9") (pin "14") (pinfunction "SER_14") (pintype "input"))
    )
    (net (code "198") (name "Net-(IC10-QH')") (class "Default")
      (node (ref "IC10") (pin "9") (pinfunction "QH'_9") (pintype "tri_state"))
      (node (ref "IC11") (pin "14") (pinfunction "SER_14") (pintype "input"))
    )
    (net (code "199") (name "Net-(IC10-SER)") (class "Default")
      (node (ref "IC10") (pin "14") (pinfunction "SER_14") (pintype "input"))
      (node (ref "IC9") (pin "9") (pinfunction "QH'_9") (pintype "tri_state"))
    )
    (net (code "200") (name "Net-(IC11-QH')") (class "Default")
      (node (ref "IC11") (pin "9") (pinfunction "QH'_9") (pintype "tri_state"))
      (node (ref "IC16") (pin "14") (pinfunction "SER_14") (pintype "input"))
    )
    (net (code "201") (name "Net-(LED1-PadA)") (class "Default")
      (node (ref "LED1") (pin "A") (pinfunction "A_A") (pintype "passive"))
      (node (ref "R8") (pin "2") (pinfunction "2_2") (pintype "passive"))
    )
    (net (code "202") (name "Net-(LED2-PadA)") (class "Default")
      (node (ref "LED2") (pin "A") (pinfunction "A_A") (pintype "passive"))
      (node (ref "R15") (pin "2") (pinfunction "2_2") (pintype "passive"))
    )
    (net (code "203") (name "Net-(LED3-PadA)") (class "Default")
      (node (ref "LED3") (pin "A") (pinfunction "A_A") (pintype "passive"))
      (node (ref "R16") (pin "2") (pinfunction "2_2") (pintype "passive"))
    )
    (net (code "204") (name "Net-(LED4-PadA)") (class "Default")
      (node (ref "LED4") (pin "A") (pinfunction "A_A") (pintype "passive"))
      (node (ref "R17") (pin "2") (pinfunction "2_2") (pintype "passive"))
    )
    (net (code "205") (name "Net-(LED5-PadA)") (class "Default")
      (node (ref "LED5") (pin "A") (pinfunction "A_A") (pintype "passive"))
      (node (ref "R30") (pin "2") (pinfunction "2_2") (pintype "passive"))
    )
    (net (code "206") (name "Net-(LED6-PadA)") (class "Default")
      (node (ref "LED6") (pin "A") (pinfunction "A_A") (pintype "passive"))
      (node (ref "R24") (pin "2") (pinfunction "2_2") (pintype "passive"))
    )
    (net (code "207") (name "Net-(U2-BST)") (class "Default")
      (node (ref "C13") (pin "1") (pinfunction "1_1") (pintype "passive"))
      (node (ref "U2") (pin "8") (pinfunction "BST_8") (pintype "passive"))
    )
    (net (code "208") (name "Net-(U2-COMP)") (class "Default")
      (node (ref "C12") (pin "1") (pinfunction "1_1") (pintype "passive"))
      (node (ref "U2") (pin "3") (pinfunction "COMP_3") (pintype "passive"))
    )
    (net (code "209") (name "Net-(U2-EN)") (class "Default")
      (node (ref "R2") (pin "2") (pinfunction "2_2") (pintype "passive"))
      (node (ref "R7") (pin "2") (pinfunction "2_2") (pintype "passive"))
      (node (ref "U2") (pin "2") (pinfunction "EN_2") (pintype "input"))
    )
    (net (code "210") (name "Net-(U2-FB)") (class "Default")
      (node (ref "R5") (pin "2") (pinfunction "2_2") (pintype "passive"))
      (node (ref "R6") (pin "2") (pinfunction "2_2") (pintype "passive"))
      (node (ref "U2") (pin "4") (pinfunction "FB_4") (pintype "input"))
    )
    (net (code "211") (name "Net-(U2-FREQ)") (class "Default")
      (node (ref "R3") (pin "2") (pinfunction "2_2") (pintype "passive"))
      (node (ref "U2") (pin "6") (pinfunction "FREQ_6") (pintype "passive"))
    )
    (net (code "212") (name "Net-(U2-SW)") (class "Default")
      (node (ref "C13") (pin "2") (pinfunction "2_2") (pintype "passive"))
      (node (ref "D1") (pin "C") (pinfunction "C_C") (pintype "passive"))
      (node (ref "U$5") (pin "2") (pinfunction "2_2") (pintype "passive"))
      (node (ref "U2") (pin "1") (pinfunction "SW_1") (pintype "output"))
    )
    (net (code "213") (name "Net-(U2-VIN)") (class "Default")
      (node (ref "C10") (pin "1") (pinfunction "1_1") (pintype "passive"))
      (node (ref "C51") (pin "1") (pinfunction "1_1") (pintype "passive"))
      (node (ref "R1") (pin "1") (pinfunction "1_1") (pintype "passive"))
      (node (ref "R2") (pin "1") (pinfunction "1_1") (pintype "passive"))
      (node (ref "U2") (pin "7") (pinfunction "VIN_7") (pintype "input"))
    )
    (net (code "214") (name "Net-(U3-BST)") (class "Default")
      (node (ref "C7") (pin "1") (pinfunction "1_1") (pintype "passive"))
      (node (ref "U3") (pin "8") (pinfunction "BST_8") (pintype "passive"))
    )
    (net (code "215") (name "Net-(U3-COMP)") (class "Default")
      (node (ref "C6") (pin "1") (pinfunction "1_1") (pintype "passive"))
      (node (ref "U3") (pin "3") (pinfunction "COMP_3") (pintype "passive"))
    )
    (net (code "216") (name "Net-(U3-EN)") (class "Default")
      (node (ref "R10") (pin "2") (pinfunction "2_2") (pintype "passive"))
      (node (ref "R41") (pin "2") (pinfunction "2_2") (pintype "passive"))
      (node (ref "U3") (pin "2") (pinfunction "EN_2") (pintype "input"))
    )
    (net (code "217") (name "Net-(U3-FB)") (class "Default")
      (node (ref "R13") (pin "2") (pinfunction "2_2") (pintype "passive"))
      (node (ref "R14") (pin "2") (pinfunction "2_2") (pintype "passive"))
      (node (ref "U3") (pin "4") (pinfunction "FB_4") (pintype "input"))
    )
    (net (code "218") (name "Net-(U3-FREQ)") (class "Default")
      (node (ref "R11") (pin "2") (pinfunction "2_2") (pintype "passive"))
      (node (ref "U3") (pin "6") (pinfunction "FREQ_6") (pintype "passive"))
    )
    (net (code "219") (name "Net-(U3-SW)") (class "Default")
      (node (ref "C7") (pin "2") (pinfunction "2_2") (pintype "passive"))
      (node (ref "D2") (pin "C") (pinfunction "C_C") (pintype "passive"))
      (node (ref "U$4") (pin "2") (pinfunction "2_2") (pintype "passive"))
      (node (ref "U3") (pin "1") (pinfunction "SW_1") (pintype "output"))
    )
    (net (code "220") (name "Net-(U3-VIN)") (class "Default")
      (node (ref "C11") (pin "1") (pinfunction "1_1") (pintype "passive"))
      (node (ref "C50") (pin "1") (pinfunction "1_1") (pintype "passive"))
      (node (ref "R10") (pin "1") (pinfunction "1_1") (pintype "passive"))
      (node (ref "R9") (pin "1") (pinfunction "1_1") (pintype "passive"))
      (node (ref "U3") (pin "7") (pinfunction "VIN_7") (pintype "input"))
    )
    (net (code "221") (name "O1") (class "Default")
      (node (ref "D27") (pin "A") (pinfunction "A_A") (pintype "passive"))
      (node (ref "IC1") (pin "15") (pinfunction "QA_15") (pintype "tri_state"))
    )
    (net (code "222") (name "O2") (class "Default")
      (node (ref "D26") (pin "A") (pinfunction "A_A") (pintype "passive"))
      (node (ref "IC1") (pin "1") (pinfunction "QB_1") (pintype "tri_state"))
    )
    (net (code "223") (name "O3") (class "Default")
      (node (ref "D25") (pin "A") (pinfunction "A_A") (pintype "passive"))
      (node (ref "IC1") (pin "2") (pinfunction "QC_2") (pintype "tri_state"))
    )
    (net (code "224") (name "O4") (class "Default")
      (node (ref "D24") (pin "A") (pinfunction "A_A") (pintype "passive"))
      (node (ref "IC1") (pin "3") (pinfunction "QD_3") (pintype "tri_state"))
    )
    (net (code "225") (name "O5") (class "Default")
      (node (ref "D23") (pin "A") (pinfunction "A_A") (pintype "passive"))
      (node (ref "IC1") (pin "4") (pinfunction "QE_4") (pintype "tri_state"))
    )
    (net (code "226") (name "O6") (class "Default")
      (node (ref "D22") (pin "A") (pinfunction "A_A") (pintype "passive"))
      (node (ref "IC1") (pin "5") (pinfunction "QF_5") (pintype "tri_state"))
    )
    (net (code "227") (name "O7") (class "Default")
      (node (ref "D21") (pin "A") (pinfunction "A_A") (pintype "passive"))
      (node (ref "IC1") (pin "6") (pinfunction "QG_6") (pintype "tri_state"))
    )
    (net (code "228") (name "O8") (class "Default")
      (node (ref "D20") (pin "A") (pinfunction "A_A") (pintype "passive"))
      (node (ref "IC1") (pin "7") (pinfunction "QH_7") (pintype "tri_state"))
    )
    (net (code "229") (name "O9") (class "Default")
      (node (ref "D18") (pin "A") (pinfunction "A_A") (pintype "passive"))
      (node (ref "IC3") (pin "15") (pinfunction "QA_15") (pintype "tri_state"))
    )
    (net (code "230") (name "O10") (class "Default")
      (node (ref "D17") (pin "A") (pinfunction "A_A") (pintype "passive"))
      (node (ref "IC3") (pin "1") (pinfunction "QB_1") (pintype "tri_state"))
    )
    (net (code "231") (name "O11") (class "Default")
      (node (ref "D16") (pin "A") (pinfunction "A_A") (pintype "passive"))
      (node (ref "IC3") (pin "2") (pinfunction "QC_2") (pintype "tri_state"))
    )
    (net (code "232") (name "O12") (class "Default")
      (node (ref "D15") (pin "A") (pinfunction "A_A") (pintype "passive"))
      (node (ref "IC3") (pin "3") (pinfunction "QD_3") (pintype "tri_state"))
    )
    (net (code "233") (name "O13") (class "Default")
      (node (ref "D14") (pin "A") (pinfunction "A_A") (pintype "passive"))
      (node (ref "IC3") (pin "4") (pinfunction "QE_4") (pintype "tri_state"))
    )
    (net (code "234") (name "O14") (class "Default")
      (node (ref "D28") (pin "A") (pinfunction "A_A") (pintype "passive"))
      (node (ref "IC3") (pin "5") (pinfunction "QF_5") (pintype "tri_state"))
    )
    (net (code "235") (name "O15") (class "Default")
      (node (ref "D29") (pin "A") (pinfunction "A_A") (pintype "passive"))
      (node (ref "IC3") (pin "6") (pinfunction "QG_6") (pintype "tri_state"))
    )
    (net (code "236") (name "O16") (class "Default")
      (node (ref "D30") (pin "A") (pinfunction "A_A") (pintype "passive"))
      (node (ref "IC3") (pin "7") (pinfunction "QH_7") (pintype "tri_state"))
    )
    (net (code "237") (name "O17") (class "Default")
      (node (ref "D31") (pin "A") (pinfunction "A_A") (pintype "passive"))
      (node (ref "IC4") (pin "15") (pinfunction "QA_15") (pintype "tri_state"))
    )
    (net (code "238") (name "O18") (class "Default")
      (node (ref "D32") (pin "A") (pinfunction "A_A") (pintype "passive"))
      (node (ref "IC4") (pin "1") (pinfunction "QB_1") (pintype "tri_state"))
    )
    (net (code "239") (name "O19") (class "Default")
      (node (ref "D33") (pin "A") (pinfunction "A_A") (pintype "passive"))
      (node (ref "IC4") (pin "2") (pinfunction "QC_2") (pintype "tri_state"))
    )
    (net (code "240") (name "O20") (class "Default")
      (node (ref "D34") (pin "A") (pinfunction "A_A") (pintype "passive"))
      (node (ref "IC4") (pin "3") (pinfunction "QD_3") (pintype "tri_state"))
    )
    (net (code "241") (name "O21") (class "Default")
      (node (ref "D35") (pin "A") (pinfunction "A_A") (pintype "passive"))
      (node (ref "IC4") (pin "4") (pinfunction "QE_4") (pintype "tri_state"))
    )
    (net (code "242") (name "O22") (class "Default")
      (node (ref "D36") (pin "A") (pinfunction "A_A") (pintype "passive"))
      (node (ref "IC4") (pin "5") (pinfunction "QF_5") (pintype "tri_state"))
    )
    (net (code "243") (name "O23") (class "Default")
      (node (ref "D37") (pin "A") (pinfunction "A_A") (pintype "passive"))
      (node (ref "IC4") (pin "6") (pinfunction "QG_6") (pintype "tri_state"))
    )
    (net (code "244") (name "O24") (class "Default")
      (node (ref "D38") (pin "A") (pinfunction "A_A") (pintype "passive"))
      (node (ref "IC4") (pin "7") (pinfunction "QH_7") (pintype "tri_state"))
    )
    (net (code "245") (name "O25") (class "Default")
      (node (ref "D39") (pin "A") (pinfunction "A_A") (pintype "passive"))
      (node (ref "IC5") (pin "15") (pinfunction "QA_15") (pintype "tri_state"))
    )
    (net (code "246") (name "O26") (class "Default")
      (node (ref "D40") (pin "A") (pinfunction "A_A") (pintype "passive"))
      (node (ref "IC5") (pin "1") (pinfunction "QB_1") (pintype "tri_state"))
    )
    (net (code "247") (name "O27") (class "Default")
      (node (ref "D53") (pin "A") (pinfunction "A_A") (pintype "passive"))
      (node (ref "IC5") (pin "2") (pinfunction "QC_2") (pintype "tri_state"))
    )
    (net (code "248") (name "O28") (class "Default")
      (node (ref "D52") (pin "A") (pinfunction "A_A") (pintype "passive"))
      (node (ref "IC5") (pin "3") (pinfunction "QD_3") (pintype "tri_state"))
    )
    (net (code "249") (name "O29") (class "Default")
      (node (ref "D51") (pin "A") (pinfunction "A_A") (pintype "passive"))
      (node (ref "IC5") (pin "4") (pinfunction "QE_4") (pintype "tri_state"))
    )
    (net (code "250") (name "O30") (class "Default")
      (node (ref "D50") (pin "A") (pinfunction "A_A") (pintype "passive"))
      (node (ref "IC5") (pin "5") (pinfunction "QF_5") (pintype "tri_state"))
    )
    (net (code "251") (name "O31") (class "Default")
      (node (ref "D49") (pin "A") (pinfunction "A_A") (pintype "passive"))
      (node (ref "IC5") (pin "6") (pinfunction "QG_6") (pintype "tri_state"))
    )
    (net (code "252") (name "O32") (class "Default")
      (node (ref "D48") (pin "A") (pinfunction "A_A") (pintype "passive"))
      (node (ref "IC5") (pin "7") (pinfunction "QH_7") (pintype "tri_state"))
    )
    (net (code "253") (name "O33") (class "Default")
      (node (ref "D47") (pin "A") (pinfunction "A_A") (pintype "passive"))
      (node (ref "IC6") (pin "15") (pinfunction "QA_15") (pintype "tri_state"))
    )
    (net (code "254") (name "O34") (class "Default")
      (node (ref "D46") (pin "A") (pinfunction "A_A") (pintype "passive"))
      (node (ref "IC6") (pin "1") (pinfunction "QB_1") (pintype "tri_state"))
    )
    (net (code "255") (name "O35") (class "Default")
      (node (ref "D45") (pin "A") (pinfunction "A_A") (pintype "passive"))
      (node (ref "IC6") (pin "2") (pinfunction "QC_2") (pintype "tri_state"))
    )
    (net (code "256") (name "O36") (class "Default")
      (node (ref "D44") (pin "A") (pinfunction "A_A") (pintype "passive"))
      (node (ref "IC6") (pin "3") (pinfunction "QD_3") (pintype "tri_state"))
    )
    (net (code "257") (name "O37") (class "Default")
      (node (ref "D43") (pin "A") (pinfunction "A_A") (pintype "passive"))
      (node (ref "IC6") (pin "4") (pinfunction "QE_4") (pintype "tri_state"))
    )
    (net (code "258") (name "O38") (class "Default")
      (node (ref "D42") (pin "A") (pinfunction "A_A") (pintype "passive"))
      (node (ref "IC6") (pin "5") (pinfunction "QF_5") (pintype "tri_state"))
    )
    (net (code "259") (name "O39") (class "Default")
      (node (ref "D41") (pin "A") (pinfunction "A_A") (pintype "passive"))
      (node (ref "IC6") (pin "6") (pinfunction "QG_6") (pintype "tri_state"))
    )
    (net (code "260") (name "O40") (class "Default")
      (node (ref "D54") (pin "A") (pinfunction "A_A") (pintype "passive"))
      (node (ref "IC6") (pin "7") (pinfunction "QH_7") (pintype "tri_state"))
    )
    (net (code "261") (name "O41") (class "Default")
      (node (ref "D55") (pin "A") (pinfunction "A_A") (pintype "passive"))
      (node (ref "IC7") (pin "15") (pinfunction "QA_15") (pintype "tri_state"))
    )
    (net (code "262") (name "O42") (class "Default")
      (node (ref "D56") (pin "A") (pinfunction "A_A") (pintype "passive"))
      (node (ref "IC7") (pin "1") (pinfunction "QB_1") (pintype "tri_state"))
    )
    (net (code "263") (name "O43") (class "Default")
      (node (ref "D57") (pin "A") (pinfunction "A_A") (pintype "passive"))
      (node (ref "IC7") (pin "2") (pinfunction "QC_2") (pintype "tri_state"))
    )
    (net (code "264") (name "O44") (class "Default")
      (node (ref "D58") (pin "A") (pinfunction "A_A") (pintype "passive"))
      (node (ref "IC7") (pin "3") (pinfunction "QD_3") (pintype "tri_state"))
    )
    (net (code "265") (name "O45") (class "Default")
      (node (ref "D59") (pin "A") (pinfunction "A_A") (pintype "passive"))
      (node (ref "IC7") (pin "4") (pinfunction "QE_4") (pintype "tri_state"))
    )
    (net (code "266") (name "O46") (class "Default")
      (node (ref "D60") (pin "A") (pinfunction "A_A") (pintype "passive"))
      (node (ref "IC7") (pin "5") (pinfunction "QF_5") (pintype "tri_state"))
    )
    (net (code "267") (name "O47") (class "Default")
      (node (ref "D61") (pin "A") (pinfunction "A_A") (pintype "passive"))
      (node (ref "IC7") (pin "6") (pinfunction "QG_6") (pintype "tri_state"))
    )
    (net (code "268") (name "O48") (class "Default")
      (node (ref "D62") (pin "A") (pinfunction "A_A") (pintype "passive"))
      (node (ref "IC7") (pin "7") (pinfunction "QH_7") (pintype "tri_state"))
    )
    (net (code "269") (name "O49") (class "Default")
      (node (ref "D63") (pin "A") (pinfunction "A_A") (pintype "passive"))
      (node (ref "IC8") (pin "15") (pinfunction "QA_15") (pintype "tri_state"))
    )
    (net (code "270") (name "O50") (class "Default")
      (node (ref "D64") (pin "A") (pinfunction "A_A") (pintype "passive"))
      (node (ref "IC8") (pin "1") (pinfunction "QB_1") (pintype "tri_state"))
    )
    (net (code "271") (name "O51") (class "Default")
      (node (ref "D65") (pin "A") (pinfunction "A_A") (pintype "passive"))
      (node (ref "IC8") (pin "2") (pinfunction "QC_2") (pintype "tri_state"))
    )
    (net (code "272") (name "O52") (class "Default")
      (node (ref "D66") (pin "A") (pinfunction "A_A") (pintype "passive"))
      (node (ref "IC8") (pin "3") (pinfunction "QD_3") (pintype "tri_state"))
    )
    (net (code "273") (name "O53") (class "Default")
      (node (ref "D67") (pin "A") (pinfunction "A_A") (pintype "passive"))
      (node (ref "IC8") (pin "4") (pinfunction "QE_4") (pintype "tri_state"))
    )
    (net (code "274") (name "O54") (class "Default")
      (node (ref "D68") (pin "A") (pinfunction "A_A") (pintype "passive"))
      (node (ref "IC8") (pin "5") (pinfunction "QF_5") (pintype "tri_state"))
    )
    (net (code "275") (name "O55") (class "Default")
      (node (ref "D69") (pin "A") (pinfunction "A_A") (pintype "passive"))
      (node (ref "IC8") (pin "6") (pinfunction "QG_6") (pintype "tri_state"))
    )
    (net (code "276") (name "O56") (class "Default")
      (node (ref "D70") (pin "A") (pinfunction "A_A") (pintype "passive"))
      (node (ref "IC8") (pin "7") (pinfunction "QH_7") (pintype "tri_state"))
    )
    (net (code "277") (name "O57") (class "Default")
      (node (ref "D71") (pin "A") (pinfunction "A_A") (pintype "passive"))
      (node (ref "IC9") (pin "15") (pinfunction "QA_15") (pintype "tri_state"))
    )
    (net (code "278") (name "O58") (class "Default")
      (node (ref "D72") (pin "A") (pinfunction "A_A") (pintype "passive"))
      (node (ref "IC9") (pin "1") (pinfunction "QB_1") (pintype "tri_state"))
    )
    (net (code "279") (name "O59") (class "Default")
      (node (ref "D73") (pin "A") (pinfunction "A_A") (pintype "passive"))
      (node (ref "IC9") (pin "2") (pinfunction "QC_2") (pintype "tri_state"))
    )
    (net (code "280") (name "O60") (class "Default")
      (node (ref "D74") (pin "A") (pinfunction "A_A") (pintype "passive"))
      (node (ref "IC9") (pin "3") (pinfunction "QD_3") (pintype "tri_state"))
    )
    (net (code "281") (name "O61") (class "Default")
      (node (ref "D75") (pin "A") (pinfunction "A_A") (pintype "passive"))
      (node (ref "IC9") (pin "4") (pinfunction "QE_4") (pintype "tri_state"))
    )
    (net (code "282") (name "O62") (class "Default")
      (node (ref "D76") (pin "A") (pinfunction "A_A") (pintype "passive"))
      (node (ref "IC9") (pin "5") (pinfunction "QF_5") (pintype "tri_state"))
    )
    (net (code "283") (name "O63") (class "Default")
      (node (ref "D77") (pin "A") (pinfunction "A_A") (pintype "passive"))
      (node (ref "IC9") (pin "6") (pinfunction "QG_6") (pintype "tri_state"))
    )
    (net (code "284") (name "O64") (class "Default")
      (node (ref "D78") (pin "A") (pinfunction "A_A") (pintype "passive"))
      (node (ref "IC9") (pin "7") (pinfunction "QH_7") (pintype "tri_state"))
    )
    (net (code "285") (name "O65") (class "Default")
      (node (ref "D90") (pin "A") (pinfunction "A_A") (pintype "passive"))
      (node (ref "IC10") (pin "15") (pinfunction "QA_15") (pintype "tri_state"))
    )
    (net (code "286") (name "O66") (class "Default")
      (node (ref "D89") (pin "A") (pinfunction "A_A") (pintype "passive"))
      (node (ref "IC10") (pin "1") (pinfunction "QB_1") (pintype "tri_state"))
    )
    (net (code "287") (name "O67") (class "Default")
      (node (ref "D88") (pin "A") (pinfunction "A_A") (pintype "passive"))
      (node (ref "IC10") (pin "2") (pinfunction "QC_2") (pintype "tri_state"))
    )
    (net (code "288") (name "O68") (class "Default")
      (node (ref "D87") (pin "A") (pinfunction "A_A") (pintype "passive"))
      (node (ref "IC10") (pin "3") (pinfunction "QD_3") (pintype "tri_state"))
    )
    (net (code "289") (name "O69") (class "Default")
      (node (ref "D86") (pin "A") (pinfunction "A_A") (pintype "passive"))
      (node (ref "IC10") (pin "4") (pinfunction "QE_4") (pintype "tri_state"))
    )
    (net (code "290") (name "O70") (class "Default")
      (node (ref "D85") (pin "A") (pinfunction "A_A") (pintype "passive"))
      (node (ref "IC10") (pin "5") (pinfunction "QF_5") (pintype "tri_state"))
    )
    (net (code "291") (name "O71") (class "Default")
      (node (ref "D84") (pin "A") (pinfunction "A_A") (pintype "passive"))
      (node (ref "IC10") (pin "6") (pinfunction "QG_6") (pintype "tri_state"))
    )
    (net (code "292") (name "O72") (class "Default")
      (node (ref "D83") (pin "A") (pinfunction "A_A") (pintype "passive"))
      (node (ref "IC10") (pin "7") (pinfunction "QH_7") (pintype "tri_state"))
    )
    (net (code "293") (name "O73") (class "Default")
      (node (ref "D82") (pin "A") (pinfunction "A_A") (pintype "passive"))
      (node (ref "IC11") (pin "15") (pinfunction "QA_15") (pintype "tri_state"))
    )
    (net (code "294") (name "O74") (class "Default")
      (node (ref "D81") (pin "A") (pinfunction "A_A") (pintype "passive"))
      (node (ref "IC11") (pin "1") (pinfunction "QB_1") (pintype "tri_state"))
    )
    (net (code "295") (name "O75") (class "Default")
      (node (ref "D80") (pin "A") (pinfunction "A_A") (pintype "passive"))
      (node (ref "IC11") (pin "2") (pinfunction "QC_2") (pintype "tri_state"))
    )
    (net (code "296") (name "O76") (class "Default")
      (node (ref "D79") (pin "A") (pinfunction "A_A") (pintype "passive"))
      (node (ref "IC11") (pin "3") (pinfunction "QD_3") (pintype "tri_state"))
    )
    (net (code "297") (name "O81") (class "Default")
      (node (ref "D5") (pin "A") (pinfunction "A_A") (pintype "passive"))
      (node (ref "IC16") (pin "15") (pinfunction "QA_15") (pintype "tri_state"))
    )
    (net (code "298") (name "O82") (class "Default")
      (node (ref "D6") (pin "A") (pinfunction "A_A") (pintype "passive"))
      (node (ref "IC16") (pin "1") (pinfunction "QB_1") (pintype "tri_state"))
    )
    (net (code "299") (name "O83") (class "Default")
      (node (ref "D7") (pin "A") (pinfunction "A_A") (pintype "passive"))
      (node (ref "IC16") (pin "2") (pinfunction "QC_2") (pintype "tri_state"))
    )
    (net (code "300") (name "O84") (class "Default")
      (node (ref "D9") (pin "A") (pinfunction "A_A") (pintype "passive"))
      (node (ref "IC16") (pin "3") (pinfunction "QD_3") (pintype "tri_state"))
    )
    (net (code "301") (name "O85") (class "Default")
      (node (ref "D10") (pin "A") (pinfunction "A_A") (pintype "passive"))
      (node (ref "IC16") (pin "4") (pinfunction "QE_4") (pintype "tri_state"))
    )
    (net (code "302") (name "O86") (class "Default")
      (node (ref "D11") (pin "A") (pinfunction "A_A") (pintype "passive"))
      (node (ref "IC16") (pin "5") (pinfunction "QF_5") (pintype "tri_state"))
    )
    (net (code "303") (name "O87") (class "Default")
      (node (ref "D12") (pin "A") (pinfunction "A_A") (pintype "passive"))
      (node (ref "IC16") (pin "6") (pinfunction "QG_6") (pintype "tri_state"))
    )
    (net (code "304") (name "O88") (class "Default")
      (node (ref "D13") (pin "A") (pinfunction "A_A") (pintype "passive"))
      (node (ref "IC16") (pin "7") (pinfunction "QH_7") (pintype "tri_state"))
    )
    (net (code "305") (name "QH'") (class "Default")
      (node (ref "IC6") (pin "9") (pinfunction "QH'_9") (pintype "tri_state"))
      (node (ref "IC7") (pin "14") (pinfunction "SER_14") (pintype "input"))
    )
    (net (code "306") (name "RTS") (class "Default")
      (node (ref "T1") (pin "1") (pinfunction "G_1") (pintype "passive"))
      (node (ref "T2") (pin "2") (pinfunction "S_2") (pintype "passive"))
      (node (ref "U$3") (pin "14") (pinfunction "RTS_14") (pintype "bidirectional"))
    )
    (net (code "307") (name "S0") (class "Default")
      (node (ref "IC12") (pin "10") (pinfunction "S0_10") (pintype "bidirectional"))
      (node (ref "IC13") (pin "10") (pinfunction "S0_10") (pintype "bidirectional"))
      (node (ref "IC14") (pin "10") (pinfunction "S0_10") (pintype "bidirectional"))
      (node (ref "IC15") (pin "10") (pinfunction "S0_10") (pintype "bidirectional"))
      (node (ref "IC17") (pin "10") (pinfunction "S0_10") (pintype "bidirectional"))
      (node (ref "IC2") (pin "10") (pinfunction "S0_10") (pintype "bidirectional"))
      (node (ref "U1") (pin "16") (pinfunction "IO13_16") (pintype "bidirectional"))
    )
    (net (code "308") (name "S1") (class "Default")
      (node (ref "IC12") (pin "11") (pinfunction "S1_11") (pintype "bidirectional"))
      (node (ref "IC13") (pin "11") (pinfunction "S1_11") (pintype "bidirectional"))
      (node (ref "IC14") (pin "11") (pinfunction "S1_11") (pintype "bidirectional"))
      (node (ref "IC15") (pin "11") (pinfunction "S1_11") (pintype "bidirectional"))
      (node (ref "IC17") (pin "11") (pinfunction "S1_11") (pintype "bidirectional"))
      (node (ref "IC2") (pin "11") (pinfunction "S1_11") (pintype "bidirectional"))
      (node (ref "U1") (pin "14") (pinfunction "IO12_14") (pintype "bidirectional"))
    )
    (net (code "309") (name "S2") (class "Default")
      (node (ref "IC12") (pin "14") (pinfunction "S2_14") (pintype "bidirectional"))
      (node (ref "IC13") (pin "14") (pinfunction "S2_14") (pintype "bidirectional"))
      (node (ref "IC14") (pin "14") (pinfunction "S2_14") (pintype "bidirectional"))
      (node (ref "IC15") (pin "14") (pinfunction "S2_14") (pintype "bidirectional"))
      (node (ref "IC17") (pin "14") (pinfunction "S2_14") (pintype "bidirectional"))
      (node (ref "IC2") (pin "14") (pinfunction "S2_14") (pintype "bidirectional"))
      (node (ref "U1") (pin "13") (pinfunction "IO14_13") (pintype "bidirectional"))
    )
    (net (code "310") (name "S3") (class "Default")
      (node (ref "IC12") (pin "13") (pinfunction "S3_13") (pintype "bidirectional"))
      (node (ref "IC13") (pin "13") (pinfunction "S3_13") (pintype "bidirectional"))
      (node (ref "IC14") (pin "13") (pinfunction "S3_13") (pintype "bidirectional"))
      (node (ref "IC15") (pin "13") (pinfunction "S3_13") (pintype "bidirectional"))
      (node (ref "IC17") (pin "13") (pinfunction "S3_13") (pintype "bidirectional"))
      (node (ref "IC2") (pin "13") (pinfunction "S3_13") (pintype "bidirectional"))
      (node (ref "U1") (pin "31") (pinfunction "IO19_31") (pintype "bidirectional"))
    )
    (net (code "311") (name "SHCP") (class "Default")
      (node (ref "IC1") (pin "11") (pinfunction "SCLK_11") (pintype "input"))
      (node (ref "IC10") (pin "11") (pinfunction "SCLK_11") (pintype "input"))
      (node (ref "IC11") (pin "11") (pinfunction "SCLK_11") (pintype "input"))
      (node (ref "IC16") (pin "11") (pinfunction "SCLK_11") (pintype "input"))
      (node (ref "IC3") (pin "11") (pinfunction "SCLK_11") (pintype "input"))
      (node (ref "IC4") (pin "11") (pinfunction "SCLK_11") (pintype "input"))
      (node (ref "IC5") (pin "11") (pinfunction "SCLK_11") (pintype "input"))
      (node (ref "IC6") (pin "11") (pinfunction "SCLK_11") (pintype "input"))
      (node (ref "IC7") (pin "11") (pinfunction "SCLK_11") (pintype "input"))
      (node (ref "IC8") (pin "11") (pinfunction "SCLK_11") (pintype "input"))
      (node (ref "IC9") (pin "11") (pinfunction "SCLK_11") (pintype "input"))
      (node (ref "U1") (pin "30") (pinfunction "IO18_30") (pintype "bidirectional"))
    )
    (net (code "312") (name "SIG") (class "Default")
      (node (ref "IC12") (pin "1") (pinfunction "Z_1") (pintype "bidirectional"))
      (node (ref "IC13") (pin "1") (pinfunction "Z_1") (pintype "bidirectional"))
      (node (ref "IC14") (pin "1") (pinfunction "Z_1") (pintype "bidirectional"))
      (node (ref "IC15") (pin "1") (pinfunction "Z_1") (pintype "bidirectional"))
      (node (ref "IC17") (pin "1") (pinfunction "Z_1") (pintype "bidirectional"))
      (node (ref "IC2") (pin "1") (pinfunction "Z_1") (pintype "bidirectional"))
      (node (ref "U1") (pin "11") (pinfunction "IO26_11") (pintype "bidirectional"))
    )
    (net (code "313") (name "STCP") (class "Default")
      (node (ref "IC1") (pin "12") (pinfunction "RCLK_12") (pintype "input"))
      (node (ref "IC10") (pin "12") (pinfunction "RCLK_12") (pintype "input"))
      (node (ref "IC11") (pin "12") (pinfunction "RCLK_12") (pintype "input"))
      (node (ref "IC16") (pin "12") (pinfunction "RCLK_12") (pintype "input"))
      (node (ref "IC3") (pin "12") (pinfunction "RCLK_12") (pintype "input"))
      (node (ref "IC4") (pin "12") (pinfunction "RCLK_12") (pintype "input"))
      (node (ref "IC5") (pin "12") (pinfunction "RCLK_12") (pintype "input"))
      (node (ref "IC6") (pin "12") (pinfunction "RCLK_12") (pintype "input"))
      (node (ref "IC7") (pin "12") (pinfunction "RCLK_12") (pintype "input"))
      (node (ref "IC8") (pin "12") (pinfunction "RCLK_12") (pintype "input"))
      (node (ref "IC9") (pin "12") (pinfunction "RCLK_12") (pintype "input"))
      (node (ref "U1") (pin "29") (pinfunction "IO5_29") (pintype "bidirectional"))
    )
    (net (code "314") (name "XI") (class "Default")
      (node (ref "C2") (pin "1") (pinfunction "1_1") (pintype "passive"))
      (node (ref "Q1") (pin "2") (pinfunction "2_2") (pintype "passive"))
      (node (ref "U$3") (pin "7") (pinfunction "XI_7") (pintype "bidirectional"))
    )
    (net (code "315") (name "XO") (class "Default")
      (node (ref "C3") (pin "1") (pinfunction "1_1") (pintype "passive"))
      (node (ref "Q1") (pin "1") (pinfunction "1_1") (pintype "passive"))
      (node (ref "U$3") (pin "8") (pinfunction "XO_8") (pintype "bidirectional"))
    )
    (net (code "316") (name "unconnected-(IC11-QE-Pad4)") (class "Default")
      (node (ref "IC11") (pin "4") (pinfunction "QE_4") (pintype "tri_state"))
    )
    (net (code "317") (name "unconnected-(IC11-QF-Pad5)") (class "Default")
      (node (ref "IC11") (pin "5") (pinfunction "QF_5") (pintype "tri_state"))
    )
    (net (code "318") (name "unconnected-(IC11-QG-Pad6)") (class "Default")
      (node (ref "IC11") (pin "6") (pinfunction "QG_6") (pintype "tri_state"))
    )
    (net (code "319") (name "unconnected-(IC11-QH-Pad7)") (class "Default")
      (node (ref "IC11") (pin "7") (pinfunction "QH_7") (pintype "tri_state"))
    )
    (net (code "320") (name "unconnected-(IC15-Y12-Pad19)") (class "Default")
      (node (ref "IC15") (pin "19") (pinfunction "Y12_19") (pintype "bidirectional"))
    )
    (net (code "321") (name "unconnected-(IC15-Y13-Pad18)") (class "Default")
      (node (ref "IC15") (pin "18") (pinfunction "Y13_18") (pintype "bidirectional"))
    )
    (net (code "322") (name "unconnected-(IC15-Y14-Pad17)") (class "Default")
      (node (ref "IC15") (pin "17") (pinfunction "Y14_17") (pintype "bidirectional"))
    )
    (net (code "323") (name "unconnected-(IC15-Y15-Pad16)") (class "Default")
      (node (ref "IC15") (pin "16") (pinfunction "Y15_16") (pintype "bidirectional"))
    )
    (net (code "324") (name "unconnected-(IC16-QH'-Pad9)") (class "Default")
      (node (ref "IC16") (pin "9") (pinfunction "QH'_9") (pintype "tri_state"))
    )
    (net (code "325") (name "unconnected-(IC17-Y8-Pad23)") (class "Default")
      (node (ref "IC17") (pin "23") (pinfunction "Y8_23") (pintype "bidirectional"))
    )
    (net (code "326") (name "unconnected-(IC17-Y9-Pad22)") (class "Default")
      (node (ref "IC17") (pin "22") (pinfunction "Y9_22") (pintype "bidirectional"))
    )
    (net (code "327") (name "unconnected-(IC17-Y10-Pad21)") (class "Default")
      (node (ref "IC17") (pin "21") (pinfunction "Y10_21") (pintype "bidirectional"))
    )
    (net (code "328") (name "unconnected-(IC17-Y11-Pad20)") (class "Default")
      (node (ref "IC17") (pin "20") (pinfunction "Y11_20") (pintype "bidirectional"))
    )
    (net (code "329") (name "unconnected-(IC17-Y12-Pad19)") (class "Default")
      (node (ref "IC17") (pin "19") (pinfunction "Y12_19") (pintype "bidirectional"))
    )
    (net (code "330") (name "unconnected-(IC17-Y13-Pad18)") (class "Default")
      (node (ref "IC17") (pin "18") (pinfunction "Y13_18") (pintype "bidirectional"))
    )
    (net (code "331") (name "unconnected-(IC17-Y14-Pad17)") (class "Default")
      (node (ref "IC17") (pin "17") (pinfunction "Y14_17") (pintype "bidirectional"))
    )
    (net (code "332") (name "unconnected-(IC17-Y15-Pad16)") (class "Default")
      (node (ref "IC17") (pin "16") (pinfunction "Y15_16") (pintype "bidirectional"))
    )
    (net (code "333") (name "unconnected-(U$3-CTS-Pad9)") (class "Default")
      (node (ref "U$3") (pin "9") (pinfunction "CTS_9") (pintype "bidirectional"))
    )
    (net (code "334") (name "unconnected-(U$3-DCD-Pad12)") (class "Default")
      (node (ref "U$3") (pin "12") (pinfunction "DCD_12") (pintype "bidirectional"))
    )
    (net (code "335") (name "unconnected-(U$3-DSR-Pad10)") (class "Default")
      (node (ref "U$3") (pin "10") (pinfunction "DSR_10") (pintype "bidirectional"))
    )
    (net (code "336") (name "unconnected-(U$3-RI-Pad11)") (class "Default")
      (node (ref "U$3") (pin "11") (pinfunction "RI_11") (pintype "bidirectional"))
    )
    (net (code "337") (name "unconnected-(U$3-RS232-Pad15)") (class "Default")
      (node (ref "U$3") (pin "15") (pinfunction "RS232_15") (pintype "bidirectional"))
    )
    (net (code "338") (name "unconnected-(U1-IO17-Pad28)") (class "Default")
      (node (ref "U1") (pin "28") (pinfunction "IO17_28") (pintype "bidirectional"))
    )
    (net (code "339") (name "unconnected-(U1-IO21-Pad33)") (class "Default")
      (node (ref "U1") (pin "33") (pinfunction "IO21_33") (pintype "bidirectional"))
    )
    (net (code "340") (name "unconnected-(U1-IO22-Pad36)") (class "Default")
      (node (ref "U1") (pin "36") (pinfunction "IO22_36") (pintype "bidirectional"))
    )
    (net (code "341") (name "unconnected-(U1-IO32-Pad8)") (class "Default")
      (node (ref "U1") (pin "8") (pinfunction "IO32_8") (pintype "bidirectional"))
    )
    (net (code "342") (name "unconnected-(U1-IO34-Pad6)") (class "Default")
      (node (ref "U1") (pin "6") (pinfunction "IO34_6") (pintype "input"))
    )
    (net (code "343") (name "unconnected-(U1-IO35-Pad7)") (class "Default")
      (node (ref "U1") (pin "7") (pinfunction "IO35_7") (pintype "input"))
    )
    (net (code "344") (name "unconnected-(U1-NC-Pad32)") (class "Default")
      (node (ref "U1") (pin "32") (pinfunction "NC_32") (pintype "no_connect"))
    )
    (net (code "345") (name "unconnected-(U1-SCK{slash}CLK-Pad20)") (class "Default")
      (node (ref "U1") (pin "20") (pinfunction "SCK/CLK_20") (pintype "bidirectional"))
    )
    (net (code "346") (name "unconnected-(U1-SCS{slash}CMD-Pad19)") (class "Default")
      (node (ref "U1") (pin "19") (pinfunction "SCS/CMD_19") (pintype "bidirectional"))
    )
    (net (code "347") (name "unconnected-(U1-SDI{slash}SD1-Pad22)") (class "Default")
      (node (ref "U1") (pin "22") (pinfunction "SDI/SD1_22") (pintype "bidirectional"))
    )
    (net (code "348") (name "unconnected-(U1-SDO{slash}SD0-Pad21)") (class "Default")
      (node (ref "U1") (pin "21") (pinfunction "SDO/SD0_21") (pintype "bidirectional"))
    )
    (net (code "349") (name "unconnected-(U1-SENSOR_VN-Pad5)") (class "Default")
      (node (ref "U1") (pin "5") (pinfunction "SENSOR_VN_5") (pintype "input"))
    )
    (net (code "350") (name "unconnected-(U1-SENSOR_VP-Pad4)") (class "Default")
      (node (ref "U1") (pin "4") (pinfunction "SENSOR_VP_4") (pintype "input"))
    )
    (net (code "351") (name "unconnected-(U1-SHD{slash}SD2-Pad17)") (class "Default")
      (node (ref "U1") (pin "17") (pinfunction "SHD/SD2_17") (pintype "bidirectional"))
    )
    (net (code "352") (name "unconnected-(U1-SWP{slash}SD3-Pad18)") (class "Default")
      (node (ref "U1") (pin "18") (pinfunction "SWP/SD3_18") (pintype "bidirectional"))
    )
    (net (code "353") (name "unconnected-(X1-Pad1)") (class "Default")
      (node (ref "X1") (pin "1") (pinfunction "1_1") (pintype "bidirectional"))
    )
    (net (code "354") (name "unconnected-(X1-PadP$1)") (class "Default")
      (node (ref "X1") (pin "P$1") (pinfunction "P$1_P$1") (pintype "bidirectional"))
    )
    (net (code "355") (name "unconnected-(X1-PadP$2)") (class "Default")
      (node (ref "X1") (pin "P$2") (pinfunction "P$2_P$2") (pintype "bidirectional"))
    )
  )
)
